# 03_-_CPU_-_DDR3_DDR3_MEM.net
KiCad netlist of a schematic drawn in Altium Designer
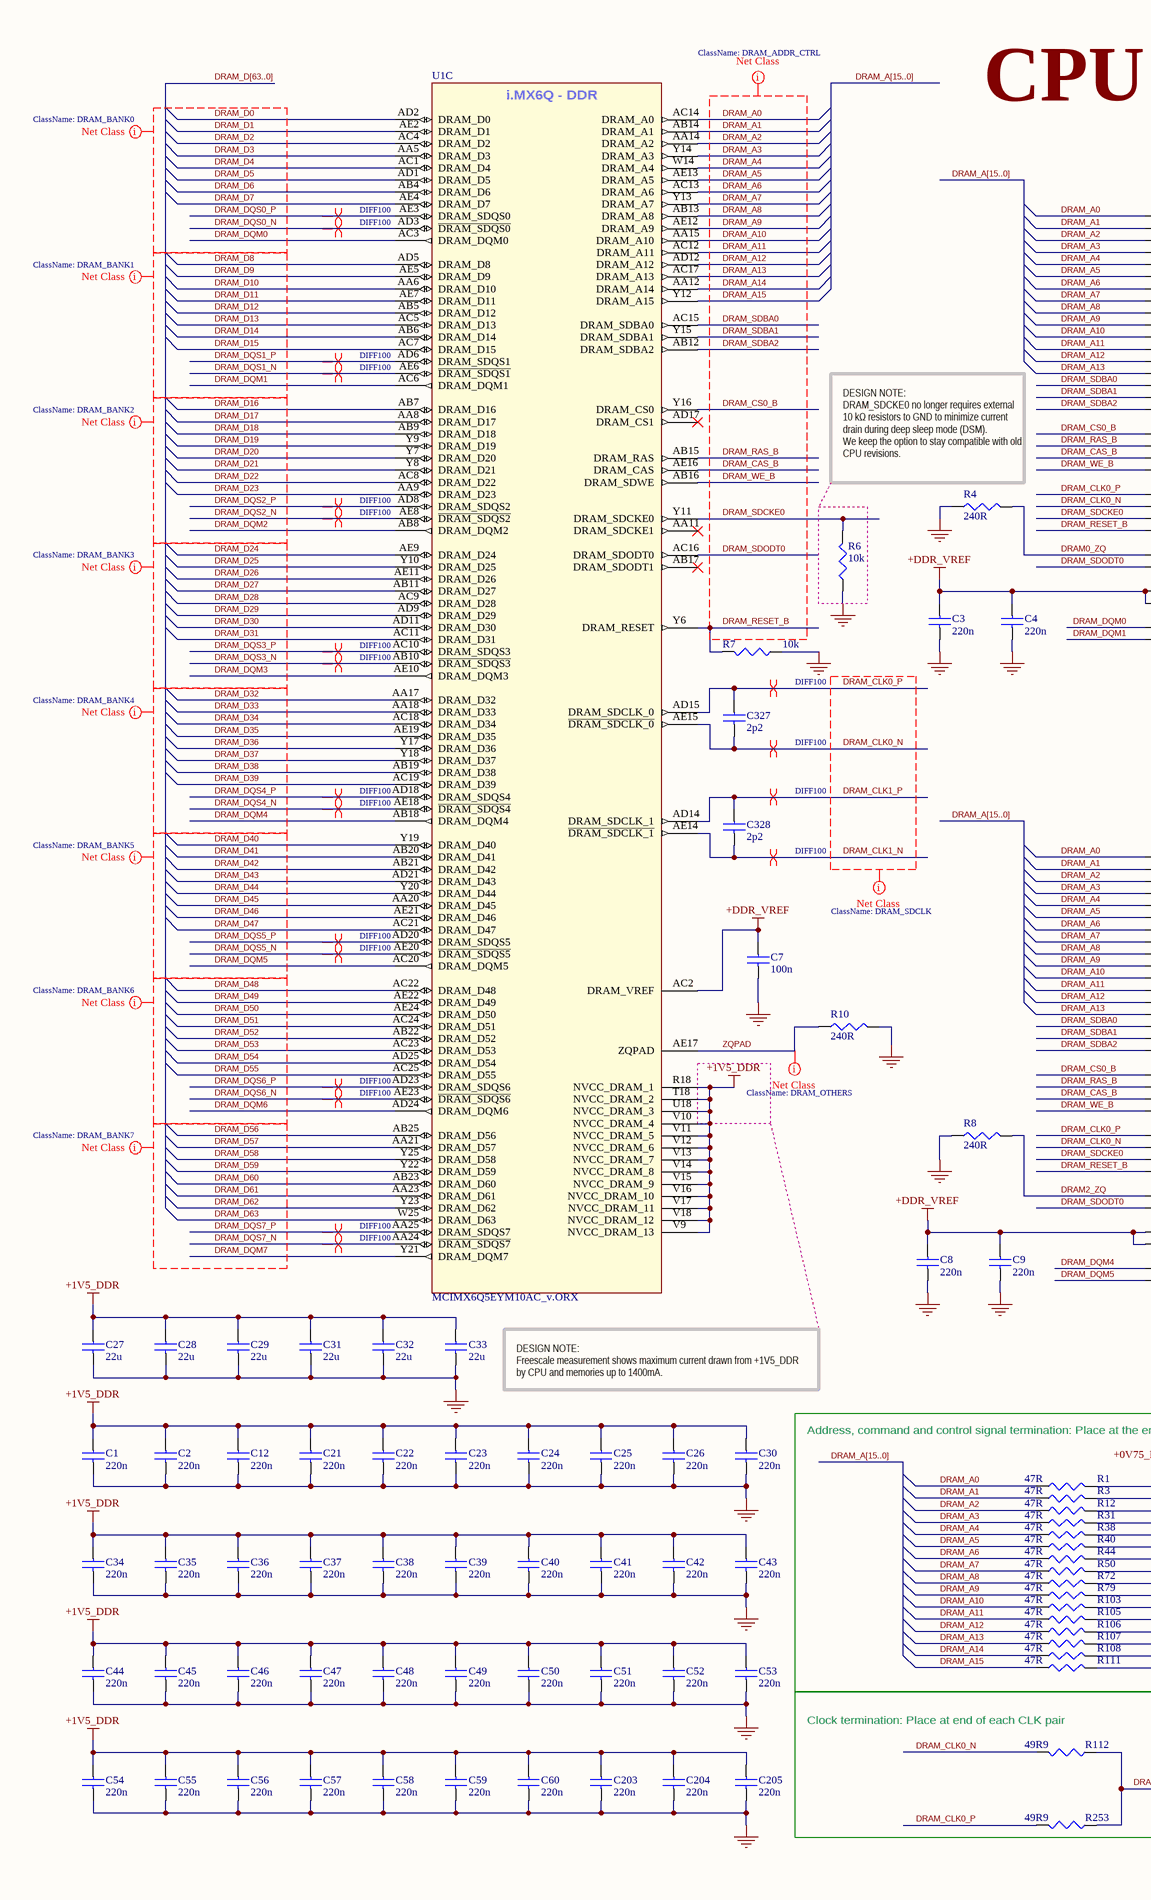
[diagram p0: [03] - CPU - DDR3, DDR3 MEM.SchDoc, left]
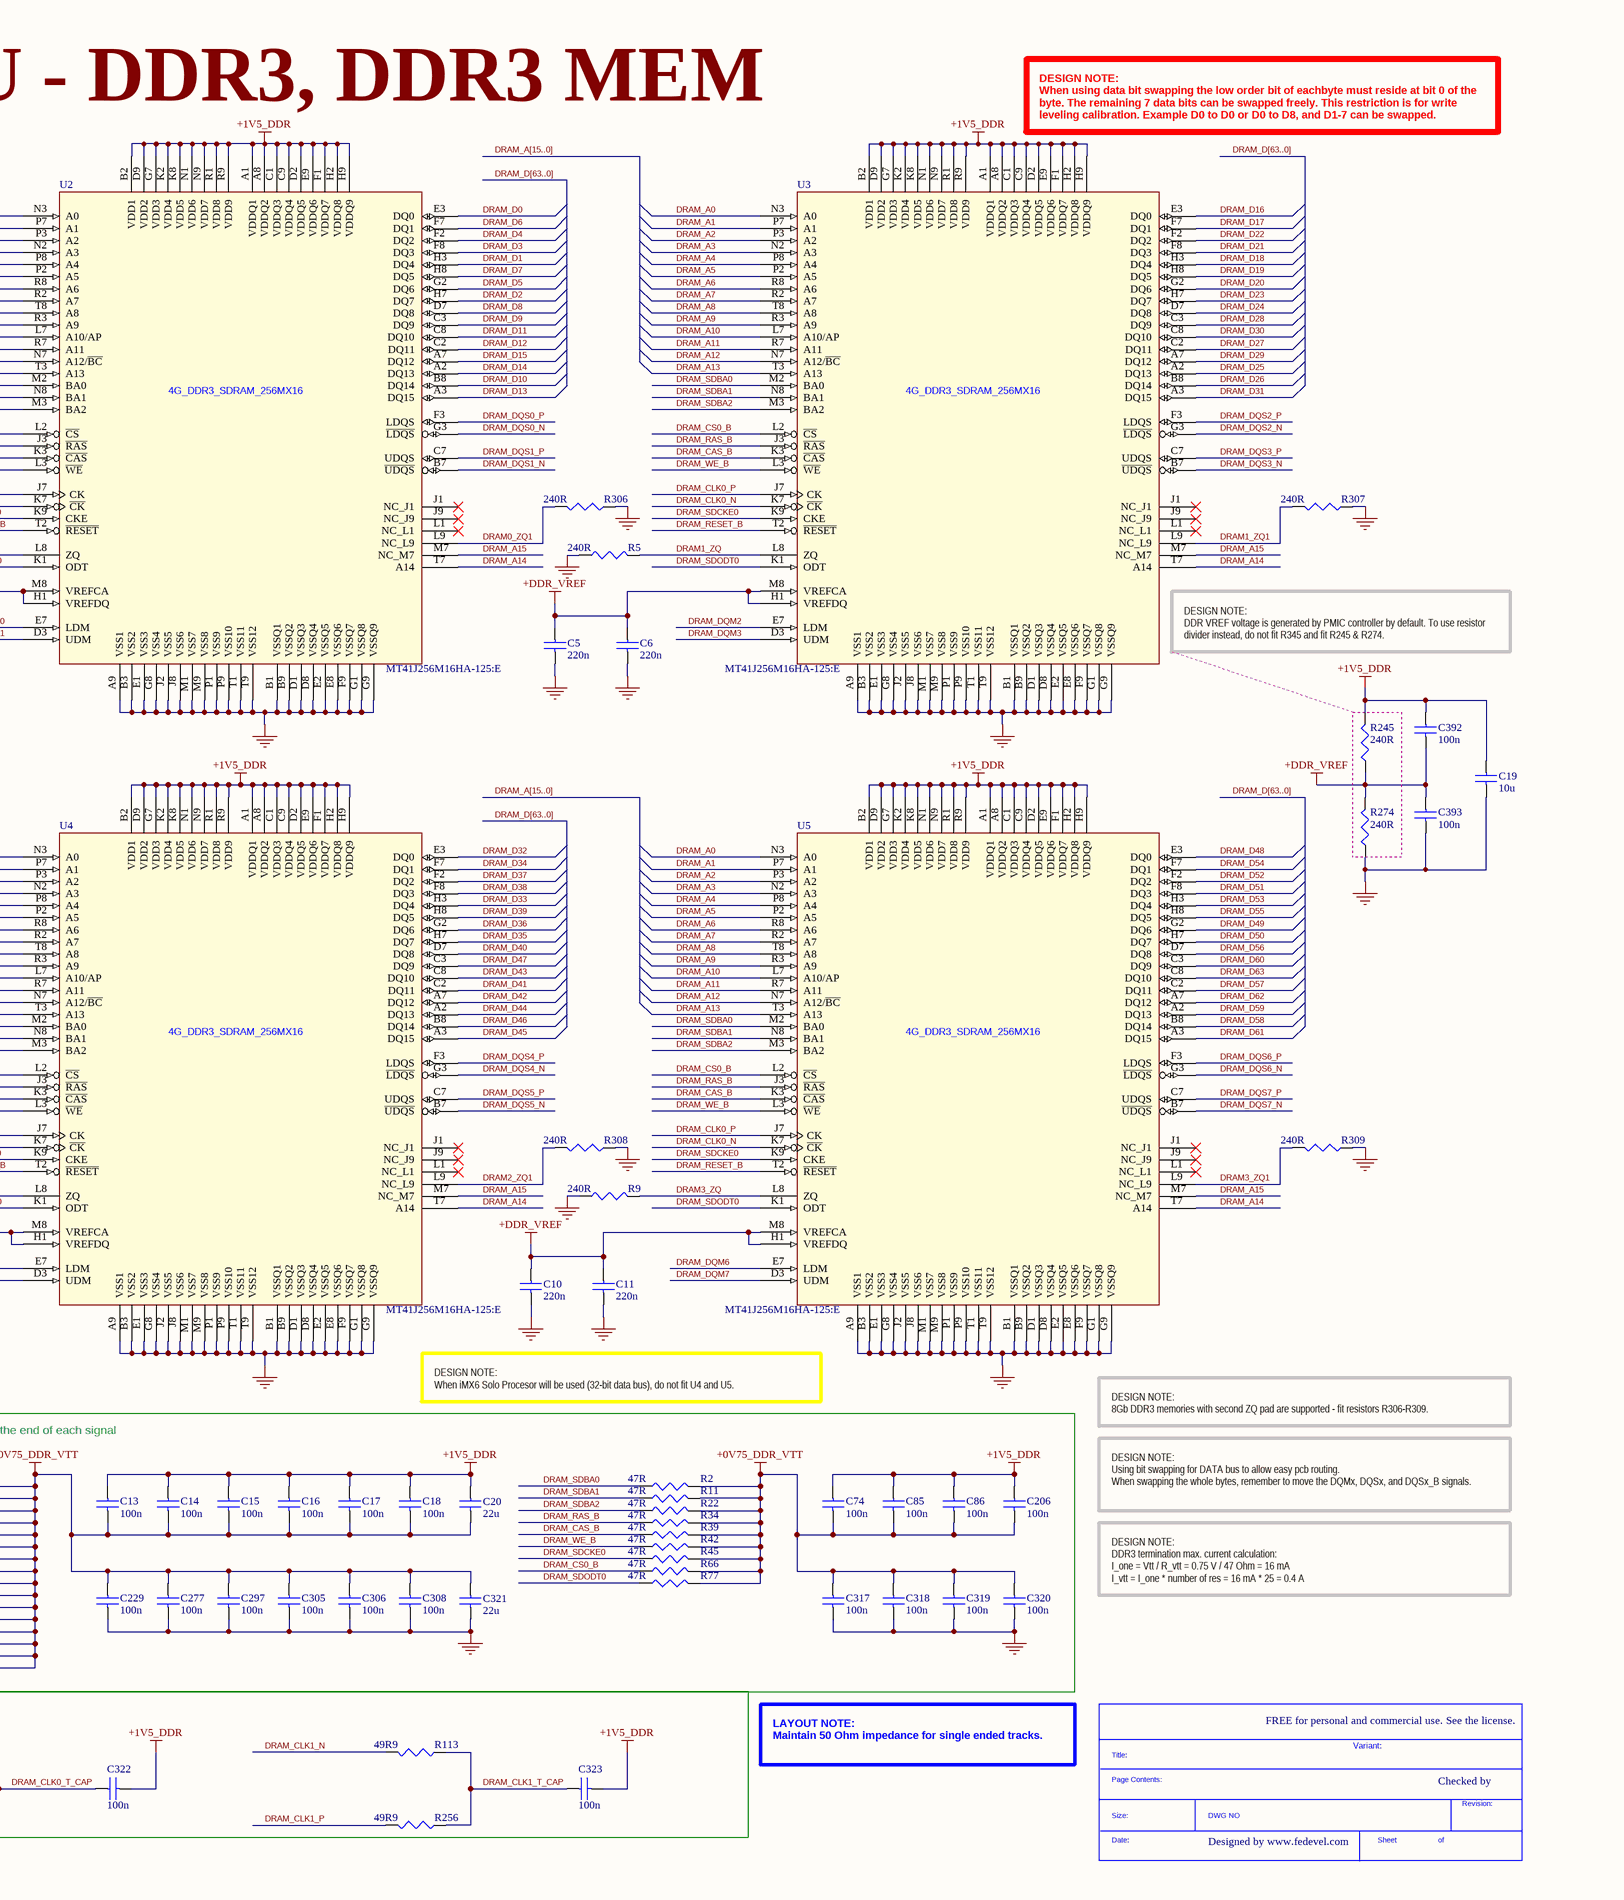
[diagram p1: [03] - CPU - DDR3, DDR3 MEM.SchDoc, right]

(export (version "E")
  (design (tool "Eeschema 10.0.6"))
  (components
    (comp (ref "C1")
      (value "220n")
      (footprint "C0201")
      (description "CAP CER 0.22UF 6.3V 20% X5R 0201")
      (fields
        (field (name "MANUFACTURER") "TDK Corporation")
        (field (name "MANUFACTURER PART NUMBER") "C0603X5R0J224M030BB")
        (field (name ".CHECKED PCB") "MM")
        (field (name ".CHECKED SCH") "MM")
        (field (name ".CREATOR") "MM")
      )
      (libsource (lib "Integrated_Library_FEDEVEL_0201") (part "C0603X5R0J224M030BB"))
    )
    (comp (ref "C2")
      (value "220n")
      (footprint "C0201")
      (description "CAP CER 0.22UF 6.3V 20% X5R 0201")
      (fields
        (field (name "MANUFACTURER") "TDK Corporation")
        (field (name "MANUFACTURER PART NUMBER") "C0603X5R0J224M030BB")
        (field (name ".CHECKED PCB") "MM")
        (field (name ".CHECKED SCH") "MM")
        (field (name ".CREATOR") "MM")
      )
      (libsource (lib "Integrated_Library_FEDEVEL_0201") (part "C0603X5R0J224M030BB"))
    )
    (comp (ref "C3")
      (value "220n")
      (footprint "C0201")
      (description "CAP CER 0.22UF 6.3V 20% X5R 0201")
      (fields
        (field (name "MANUFACTURER") "TDK Corporation")
        (field (name "MANUFACTURER PART NUMBER") "C0603X5R0J224M030BB")
        (field (name ".CHECKED PCB") "MM")
        (field (name ".CHECKED SCH") "MM")
        (field (name ".CREATOR") "MM")
      )
      (libsource (lib "Integrated_Library_FEDEVEL_0201") (part "C0603X5R0J224M030BB"))
    )
    (comp (ref "C4")
      (value "220n")
      (footprint "C0201")
      (description "CAP CER 0.22UF 6.3V 20% X5R 0201")
      (fields
        (field (name "MANUFACTURER") "TDK Corporation")
        (field (name "MANUFACTURER PART NUMBER") "C0603X5R0J224M030BB")
        (field (name ".CHECKED PCB") "MM")
        (field (name ".CHECKED SCH") "MM")
        (field (name ".CREATOR") "MM")
      )
      (libsource (lib "Integrated_Library_FEDEVEL_0201") (part "C0603X5R0J224M030BB"))
    )
    (comp (ref "C5")
      (value "220n")
      (footprint "C0201")
      (description "CAP CER 0.22UF 6.3V 20% X5R 0201")
      (fields
        (field (name "MANUFACTURER") "TDK Corporation")
        (field (name "MANUFACTURER PART NUMBER") "C0603X5R0J224M030BB")
        (field (name ".CHECKED PCB") "MM")
        (field (name ".CHECKED SCH") "MM")
        (field (name ".CREATOR") "MM")
      )
      (libsource (lib "Integrated_Library_FEDEVEL_0201") (part "C0603X5R0J224M030BB"))
    )
    (comp (ref "C6")
      (value "220n")
      (footprint "C0201")
      (description "CAP CER 0.22UF 6.3V 20% X5R 0201")
      (fields
        (field (name "MANUFACTURER") "TDK Corporation")
        (field (name "MANUFACTURER PART NUMBER") "C0603X5R0J224M030BB")
        (field (name ".CHECKED PCB") "MM")
        (field (name ".CHECKED SCH") "MM")
        (field (name ".CREATOR") "MM")
      )
      (libsource (lib "Integrated_Library_FEDEVEL_0201") (part "C0603X5R0J224M030BB"))
    )
    (comp (ref "C7")
      (value "100n")
      (footprint "C0201")
      (description "CAP CER 0.1UF 16V 10% X5R 0201")
      (fields
        (field (name "MANUFACTURER") "TDK Corporation")
        (field (name "MANUFACTURER PART NUMBER") "C0603X5R1C104K030BC")
        (field (name ".CREATOR") "MM")
        (field (name ".CHECKED PCB") "MM")
        (field (name ".CHECKED SCH") "MM")
      )
      (libsource (lib "Integrated_Library_FEDEVEL_0201") (part "C0603X5R1C104K030BC"))
    )
    (comp (ref "C8")
      (value "220n")
      (footprint "C0201")
      (description "CAP CER 0.22UF 6.3V 20% X5R 0201")
      (fields
        (field (name "MANUFACTURER") "TDK Corporation")
        (field (name "MANUFACTURER PART NUMBER") "C0603X5R0J224M030BB")
        (field (name ".CHECKED PCB") "MM")
        (field (name ".CHECKED SCH") "MM")
        (field (name ".CREATOR") "MM")
      )
      (libsource (lib "Integrated_Library_FEDEVEL_0201") (part "C0603X5R0J224M030BB"))
    )
    (comp (ref "C9")
      (value "220n")
      (footprint "C0201")
      (description "CAP CER 0.22UF 6.3V 20% X5R 0201")
      (fields
        (field (name "MANUFACTURER") "TDK Corporation")
        (field (name "MANUFACTURER PART NUMBER") "C0603X5R0J224M030BB")
        (field (name ".CHECKED PCB") "MM")
        (field (name ".CHECKED SCH") "MM")
        (field (name ".CREATOR") "MM")
      )
      (libsource (lib "Integrated_Library_FEDEVEL_0201") (part "C0603X5R0J224M030BB"))
    )
    (comp (ref "C10")
      (value "220n")
      (footprint "C0201")
      (description "CAP CER 0.22UF 6.3V 20% X5R 0201")
      (fields
        (field (name "MANUFACTURER") "TDK Corporation")
        (field (name "MANUFACTURER PART NUMBER") "C0603X5R0J224M030BB")
        (field (name ".CHECKED PCB") "MM")
        (field (name ".CHECKED SCH") "MM")
        (field (name ".CREATOR") "MM")
      )
      (libsource (lib "Integrated_Library_FEDEVEL_0201") (part "C0603X5R0J224M030BB"))
    )
    (comp (ref "C11")
      (value "220n")
      (footprint "C0201")
      (description "CAP CER 0.22UF 6.3V 20% X5R 0201")
      (fields
        (field (name "MANUFACTURER") "TDK Corporation")
        (field (name "MANUFACTURER PART NUMBER") "C0603X5R0J224M030BB")
        (field (name ".CHECKED PCB") "MM")
        (field (name ".CHECKED SCH") "MM")
        (field (name ".CREATOR") "MM")
      )
      (libsource (lib "Integrated_Library_FEDEVEL_0201") (part "C0603X5R0J224M030BB"))
    )
    (comp (ref "C12")
      (value "220n")
      (footprint "C0201")
      (description "CAP CER 0.22UF 6.3V 20% X5R 0201")
      (fields
        (field (name "MANUFACTURER") "TDK Corporation")
        (field (name "MANUFACTURER PART NUMBER") "C0603X5R0J224M030BB")
        (field (name ".CHECKED PCB") "MM")
        (field (name ".CHECKED SCH") "MM")
        (field (name ".CREATOR") "MM")
      )
      (libsource (lib "Integrated_Library_FEDEVEL_0201") (part "C0603X5R0J224M030BB"))
    )
    (comp (ref "C13")
      (value "100n")
      (footprint "C0201")
      (description "CAP CER 0.1UF 16V 10% X5R 0201")
      (fields
        (field (name "MANUFACTURER") "TDK Corporation")
        (field (name "MANUFACTURER PART NUMBER") "C0603X5R1C104K030BC")
        (field (name ".CREATOR") "MM")
        (field (name ".CHECKED PCB") "MM")
        (field (name ".CHECKED SCH") "MM")
      )
      (libsource (lib "Integrated_Library_FEDEVEL_0201") (part "C0603X5R1C104K030BC"))
    )
    (comp (ref "C14")
      (value "100n")
      (footprint "C0201")
      (description "CAP CER 0.1UF 16V 10% X5R 0201")
      (fields
        (field (name "MANUFACTURER") "TDK Corporation")
        (field (name "MANUFACTURER PART NUMBER") "C0603X5R1C104K030BC")
        (field (name ".CREATOR") "MM")
        (field (name ".CHECKED PCB") "MM")
        (field (name ".CHECKED SCH") "MM")
      )
      (libsource (lib "Integrated_Library_FEDEVEL_0201") (part "C0603X5R1C104K030BC"))
    )
    (comp (ref "C15")
      (value "100n")
      (footprint "C0201")
      (description "CAP CER 0.1UF 16V 10% X5R 0201")
      (fields
        (field (name "MANUFACTURER") "TDK Corporation")
        (field (name "MANUFACTURER PART NUMBER") "C0603X5R1C104K030BC")
        (field (name ".CREATOR") "MM")
        (field (name ".CHECKED PCB") "MM")
        (field (name ".CHECKED SCH") "MM")
      )
      (libsource (lib "Integrated_Library_FEDEVEL_0201") (part "C0603X5R1C104K030BC"))
    )
    (comp (ref "C16")
      (value "100n")
      (footprint "C0201")
      (description "CAP CER 0.1UF 16V 10% X5R 0201")
      (fields
        (field (name "MANUFACTURER") "TDK Corporation")
        (field (name "MANUFACTURER PART NUMBER") "C0603X5R1C104K030BC")
        (field (name ".CREATOR") "MM")
        (field (name ".CHECKED PCB") "MM")
        (field (name ".CHECKED SCH") "MM")
      )
      (libsource (lib "Integrated_Library_FEDEVEL_0201") (part "C0603X5R1C104K030BC"))
    )
    (comp (ref "C17")
      (value "100n")
      (footprint "C0201")
      (description "CAP CER 0.1UF 16V 10% X5R 0201")
      (fields
        (field (name "MANUFACTURER") "TDK Corporation")
        (field (name "MANUFACTURER PART NUMBER") "C0603X5R1C104K030BC")
        (field (name ".CREATOR") "MM")
        (field (name ".CHECKED PCB") "MM")
        (field (name ".CHECKED SCH") "MM")
      )
      (libsource (lib "Integrated_Library_FEDEVEL_0201") (part "C0603X5R1C104K030BC"))
    )
    (comp (ref "C18")
      (value "100n")
      (footprint "C0201")
      (description "CAP CER 0.1UF 16V 10% X5R 0201")
      (fields
        (field (name "MANUFACTURER") "TDK Corporation")
        (field (name "MANUFACTURER PART NUMBER") "C0603X5R1C104K030BC")
        (field (name ".CREATOR") "MM")
        (field (name ".CHECKED PCB") "MM")
        (field (name ".CHECKED SCH") "MM")
      )
      (libsource (lib "Integrated_Library_FEDEVEL_0201") (part "C0603X5R1C104K030BC"))
    )
    (comp (ref "C19")
      (value "10u")
      (footprint "C0603")
      (description "CAP CER 10UF 6.3V X5R 20% 0603")
      (fields
        (field (name "MANUFACTURER") "TDK Corporation")
        (field (name "MANUFACTURER PART NUMBER") "C1608X5R0J106M")
      )
      (libsource (lib "Integrated_Library_FEDEVEL_APR_2015") (part "C1608X5R0J106M"))
    )
    (comp (ref "C20")
      (value "22u")
      (footprint "C0603")
      (description "CAP CER 22UF 4V 20% X5R 0603")
      (fields
        (field (name "MANUFACTURER") "Murata Electronics North America")
        (field (name "MANUFACTURER PART NUMBER") "GRM188R60G226MEA0L")
        (field (name ".CREATOR") "MM")
      )
      (libsource (lib "Integrated_Library_FEDEVEL_APR_2015") (part "GRM188R60G226MEA0L"))
    )
    (comp (ref "C21")
      (value "220n")
      (footprint "C0201")
      (description "CAP CER 0.22UF 6.3V 20% X5R 0201")
      (fields
        (field (name "MANUFACTURER") "TDK Corporation")
        (field (name "MANUFACTURER PART NUMBER") "C0603X5R0J224M030BB")
        (field (name ".CHECKED PCB") "MM")
        (field (name ".CHECKED SCH") "MM")
        (field (name ".CREATOR") "MM")
      )
      (libsource (lib "Integrated_Library_FEDEVEL_0201") (part "C0603X5R0J224M030BB"))
    )
    (comp (ref "C22")
      (value "220n")
      (footprint "C0201")
      (description "CAP CER 0.22UF 6.3V 20% X5R 0201")
      (fields
        (field (name "MANUFACTURER") "TDK Corporation")
        (field (name "MANUFACTURER PART NUMBER") "C0603X5R0J224M030BB")
        (field (name ".CHECKED PCB") "MM")
        (field (name ".CHECKED SCH") "MM")
        (field (name ".CREATOR") "MM")
      )
      (libsource (lib "Integrated_Library_FEDEVEL_0201") (part "C0603X5R0J224M030BB"))
    )
    (comp (ref "C23")
      (value "220n")
      (footprint "C0201")
      (description "CAP CER 0.22UF 6.3V 20% X5R 0201")
      (fields
        (field (name "MANUFACTURER") "TDK Corporation")
        (field (name "MANUFACTURER PART NUMBER") "C0603X5R0J224M030BB")
        (field (name ".CHECKED PCB") "MM")
        (field (name ".CHECKED SCH") "MM")
        (field (name ".CREATOR") "MM")
      )
      (libsource (lib "Integrated_Library_FEDEVEL_0201") (part "C0603X5R0J224M030BB"))
    )
    (comp (ref "C24")
      (value "220n")
      (footprint "C0201")
      (description "CAP CER 0.22UF 6.3V 20% X5R 0201")
      (fields
        (field (name "MANUFACTURER") "TDK Corporation")
        (field (name "MANUFACTURER PART NUMBER") "C0603X5R0J224M030BB")
        (field (name ".CHECKED PCB") "MM")
        (field (name ".CHECKED SCH") "MM")
        (field (name ".CREATOR") "MM")
      )
      (libsource (lib "Integrated_Library_FEDEVEL_0201") (part "C0603X5R0J224M030BB"))
    )
    (comp (ref "C25")
      (value "220n")
      (footprint "C0201")
      (description "CAP CER 0.22UF 6.3V 20% X5R 0201")
      (fields
        (field (name "MANUFACTURER") "TDK Corporation")
        (field (name "MANUFACTURER PART NUMBER") "C0603X5R0J224M030BB")
        (field (name ".CHECKED PCB") "MM")
        (field (name ".CHECKED SCH") "MM")
        (field (name ".CREATOR") "MM")
      )
      (libsource (lib "Integrated_Library_FEDEVEL_0201") (part "C0603X5R0J224M030BB"))
    )
    (comp (ref "C26")
      (value "220n")
      (footprint "C0201")
      (description "CAP CER 0.22UF 6.3V 20% X5R 0201")
      (fields
        (field (name "MANUFACTURER") "TDK Corporation")
        (field (name "MANUFACTURER PART NUMBER") "C0603X5R0J224M030BB")
        (field (name ".CHECKED PCB") "MM")
        (field (name ".CHECKED SCH") "MM")
        (field (name ".CREATOR") "MM")
      )
      (libsource (lib "Integrated_Library_FEDEVEL_0201") (part "C0603X5R0J224M030BB"))
    )
    (comp (ref "C27")
      (value "22u")
      (footprint "C0603")
      (description "CAP CER 22UF 4V 20% X5R 0603")
      (fields
        (field (name "MANUFACTURER") "Murata Electronics North America")
        (field (name "MANUFACTURER PART NUMBER") "GRM188R60G226MEA0L")
        (field (name ".CREATOR") "MM")
      )
      (libsource (lib "Integrated_Library_FEDEVEL_APR_2015") (part "GRM188R60G226MEA0L"))
    )
    (comp (ref "C28")
      (value "22u")
      (footprint "C0603")
      (description "CAP CER 22UF 4V 20% X5R 0603")
      (fields
        (field (name "MANUFACTURER") "Murata Electronics North America")
        (field (name "MANUFACTURER PART NUMBER") "GRM188R60G226MEA0L")
        (field (name ".CREATOR") "MM")
      )
      (libsource (lib "Integrated_Library_FEDEVEL_APR_2015") (part "GRM188R60G226MEA0L"))
    )
    (comp (ref "C29")
      (value "22u")
      (footprint "C0603")
      (description "CAP CER 22UF 4V 20% X5R 0603")
      (fields
        (field (name "MANUFACTURER") "Murata Electronics North America")
        (field (name "MANUFACTURER PART NUMBER") "GRM188R60G226MEA0L")
        (field (name ".CREATOR") "MM")
      )
      (libsource (lib "Integrated_Library_FEDEVEL_APR_2015") (part "GRM188R60G226MEA0L"))
    )
    (comp (ref "C30")
      (value "220n")
      (footprint "C0201")
      (description "CAP CER 0.22UF 6.3V 20% X5R 0201")
      (fields
        (field (name "MANUFACTURER") "TDK Corporation")
        (field (name "MANUFACTURER PART NUMBER") "C0603X5R0J224M030BB")
        (field (name ".CHECKED PCB") "MM")
        (field (name ".CHECKED SCH") "MM")
        (field (name ".CREATOR") "MM")
      )
      (libsource (lib "Integrated_Library_FEDEVEL_0201") (part "C0603X5R0J224M030BB"))
    )
    (comp (ref "C31")
      (value "22u")
      (footprint "C0603")
      (description "CAP CER 22UF 4V 20% X5R 0603")
      (fields
        (field (name "MANUFACTURER") "Murata Electronics North America")
        (field (name "MANUFACTURER PART NUMBER") "GRM188R60G226MEA0L")
        (field (name ".CREATOR") "MM")
      )
      (libsource (lib "Integrated_Library_FEDEVEL_APR_2015") (part "GRM188R60G226MEA0L"))
    )
    (comp (ref "C32")
      (value "22u")
      (footprint "C0603")
      (description "CAP CER 22UF 4V 20% X5R 0603")
      (fields
        (field (name "MANUFACTURER") "Murata Electronics North America")
        (field (name "MANUFACTURER PART NUMBER") "GRM188R60G226MEA0L")
        (field (name ".CREATOR") "MM")
      )
      (libsource (lib "Integrated_Library_FEDEVEL_APR_2015") (part "GRM188R60G226MEA0L"))
    )
    (comp (ref "C33")
      (value "22u")
      (footprint "C0603")
      (description "CAP CER 22UF 4V 20% X5R 0603")
      (fields
        (field (name "MANUFACTURER") "Murata Electronics North America")
        (field (name "MANUFACTURER PART NUMBER") "GRM188R60G226MEA0L")
        (field (name ".CREATOR") "MM")
      )
      (libsource (lib "Integrated_Library_FEDEVEL_APR_2015") (part "GRM188R60G226MEA0L"))
    )
    (comp (ref "C34")
      (value "220n")
      (footprint "C0201")
      (description "CAP CER 0.22UF 6.3V 20% X5R 0201")
      (fields
        (field (name "MANUFACTURER") "TDK Corporation")
        (field (name "MANUFACTURER PART NUMBER") "C0603X5R0J224M030BB")
        (field (name ".CHECKED PCB") "MM")
        (field (name ".CHECKED SCH") "MM")
        (field (name ".CREATOR") "MM")
      )
      (libsource (lib "Integrated_Library_FEDEVEL_0201") (part "C0603X5R0J224M030BB"))
    )
    (comp (ref "C35")
      (value "220n")
      (footprint "C0201")
      (description "CAP CER 0.22UF 6.3V 20% X5R 0201")
      (fields
        (field (name "MANUFACTURER") "TDK Corporation")
        (field (name "MANUFACTURER PART NUMBER") "C0603X5R0J224M030BB")
        (field (name ".CHECKED PCB") "MM")
        (field (name ".CHECKED SCH") "MM")
        (field (name ".CREATOR") "MM")
      )
      (libsource (lib "Integrated_Library_FEDEVEL_0201") (part "C0603X5R0J224M030BB"))
    )
    (comp (ref "C36")
      (value "220n")
      (footprint "C0201")
      (description "CAP CER 0.22UF 6.3V 20% X5R 0201")
      (fields
        (field (name "MANUFACTURER") "TDK Corporation")
        (field (name "MANUFACTURER PART NUMBER") "C0603X5R0J224M030BB")
        (field (name ".CHECKED PCB") "MM")
        (field (name ".CHECKED SCH") "MM")
        (field (name ".CREATOR") "MM")
      )
      (libsource (lib "Integrated_Library_FEDEVEL_0201") (part "C0603X5R0J224M030BB"))
    )
    (comp (ref "C37")
      (value "220n")
      (footprint "C0201")
      (description "CAP CER 0.22UF 6.3V 20% X5R 0201")
      (fields
        (field (name "MANUFACTURER") "TDK Corporation")
        (field (name "MANUFACTURER PART NUMBER") "C0603X5R0J224M030BB")
        (field (name ".CHECKED PCB") "MM")
        (field (name ".CHECKED SCH") "MM")
        (field (name ".CREATOR") "MM")
      )
      (libsource (lib "Integrated_Library_FEDEVEL_0201") (part "C0603X5R0J224M030BB"))
    )
    (comp (ref "C38")
      (value "220n")
      (footprint "C0201")
      (description "CAP CER 0.22UF 6.3V 20% X5R 0201")
      (fields
        (field (name "MANUFACTURER") "TDK Corporation")
        (field (name "MANUFACTURER PART NUMBER") "C0603X5R0J224M030BB")
        (field (name ".CHECKED PCB") "MM")
        (field (name ".CHECKED SCH") "MM")
        (field (name ".CREATOR") "MM")
      )
      (libsource (lib "Integrated_Library_FEDEVEL_0201") (part "C0603X5R0J224M030BB"))
    )
    (comp (ref "C39")
      (value "220n")
      (footprint "C0201")
      (description "CAP CER 0.22UF 6.3V 20% X5R 0201")
      (fields
        (field (name "MANUFACTURER") "TDK Corporation")
        (field (name "MANUFACTURER PART NUMBER") "C0603X5R0J224M030BB")
        (field (name ".CHECKED PCB") "MM")
        (field (name ".CHECKED SCH") "MM")
        (field (name ".CREATOR") "MM")
      )
      (libsource (lib "Integrated_Library_FEDEVEL_0201") (part "C0603X5R0J224M030BB"))
    )
    (comp (ref "C40")
      (value "220n")
      (footprint "C0201")
      (description "CAP CER 0.22UF 6.3V 20% X5R 0201")
      (fields
        (field (name "MANUFACTURER") "TDK Corporation")
        (field (name "MANUFACTURER PART NUMBER") "C0603X5R0J224M030BB")
        (field (name ".CHECKED PCB") "MM")
        (field (name ".CHECKED SCH") "MM")
        (field (name ".CREATOR") "MM")
      )
      (libsource (lib "Integrated_Library_FEDEVEL_0201") (part "C0603X5R0J224M030BB"))
    )
    (comp (ref "C41")
      (value "220n")
      (footprint "C0201")
      (description "CAP CER 0.22UF 6.3V 20% X5R 0201")
      (fields
        (field (name "MANUFACTURER") "TDK Corporation")
        (field (name "MANUFACTURER PART NUMBER") "C0603X5R0J224M030BB")
        (field (name ".CHECKED PCB") "MM")
        (field (name ".CHECKED SCH") "MM")
        (field (name ".CREATOR") "MM")
      )
      (libsource (lib "Integrated_Library_FEDEVEL_0201") (part "C0603X5R0J224M030BB"))
    )
    (comp (ref "C42")
      (value "220n")
      (footprint "C0201")
      (description "CAP CER 0.22UF 6.3V 20% X5R 0201")
      (fields
        (field (name "MANUFACTURER") "TDK Corporation")
        (field (name "MANUFACTURER PART NUMBER") "C0603X5R0J224M030BB")
        (field (name ".CHECKED PCB") "MM")
        (field (name ".CHECKED SCH") "MM")
        (field (name ".CREATOR") "MM")
      )
      (libsource (lib "Integrated_Library_FEDEVEL_0201") (part "C0603X5R0J224M030BB"))
    )
    (comp (ref "C43")
      (value "220n")
      (footprint "C0201")
      (description "CAP CER 0.22UF 6.3V 20% X5R 0201")
      (fields
        (field (name "MANUFACTURER") "TDK Corporation")
        (field (name "MANUFACTURER PART NUMBER") "C0603X5R0J224M030BB")
        (field (name ".CHECKED PCB") "MM")
        (field (name ".CHECKED SCH") "MM")
        (field (name ".CREATOR") "MM")
      )
      (libsource (lib "Integrated_Library_FEDEVEL_0201") (part "C0603X5R0J224M030BB"))
    )
    (comp (ref "C44")
      (value "220n")
      (footprint "C0201")
      (description "CAP CER 0.22UF 6.3V 20% X5R 0201")
      (fields
        (field (name "MANUFACTURER") "TDK Corporation")
        (field (name "MANUFACTURER PART NUMBER") "C0603X5R0J224M030BB")
        (field (name ".CHECKED PCB") "MM")
        (field (name ".CHECKED SCH") "MM")
        (field (name ".CREATOR") "MM")
      )
      (libsource (lib "Integrated_Library_FEDEVEL_0201") (part "C0603X5R0J224M030BB"))
    )
    (comp (ref "C45")
      (value "220n")
      (footprint "C0201")
      (description "CAP CER 0.22UF 6.3V 20% X5R 0201")
      (fields
        (field (name "MANUFACTURER") "TDK Corporation")
        (field (name "MANUFACTURER PART NUMBER") "C0603X5R0J224M030BB")
        (field (name ".CHECKED PCB") "MM")
        (field (name ".CHECKED SCH") "MM")
        (field (name ".CREATOR") "MM")
      )
      (libsource (lib "Integrated_Library_FEDEVEL_0201") (part "C0603X5R0J224M030BB"))
    )
    (comp (ref "C46")
      (value "220n")
      (footprint "C0201")
      (description "CAP CER 0.22UF 6.3V 20% X5R 0201")
      (fields
        (field (name "MANUFACTURER") "TDK Corporation")
        (field (name "MANUFACTURER PART NUMBER") "C0603X5R0J224M030BB")
        (field (name ".CHECKED PCB") "MM")
        (field (name ".CHECKED SCH") "MM")
        (field (name ".CREATOR") "MM")
      )
      (libsource (lib "Integrated_Library_FEDEVEL_0201") (part "C0603X5R0J224M030BB"))
    )
    (comp (ref "C47")
      (value "220n")
      (footprint "C0201")
      (description "CAP CER 0.22UF 6.3V 20% X5R 0201")
      (fields
        (field (name "MANUFACTURER") "TDK Corporation")
        (field (name "MANUFACTURER PART NUMBER") "C0603X5R0J224M030BB")
        (field (name ".CHECKED PCB") "MM")
        (field (name ".CHECKED SCH") "MM")
        (field (name ".CREATOR") "MM")
      )
      (libsource (lib "Integrated_Library_FEDEVEL_0201") (part "C0603X5R0J224M030BB"))
    )
    (comp (ref "C48")
      (value "220n")
      (footprint "C0201")
      (description "CAP CER 0.22UF 6.3V 20% X5R 0201")
      (fields
        (field (name "MANUFACTURER") "TDK Corporation")
        (field (name "MANUFACTURER PART NUMBER") "C0603X5R0J224M030BB")
        (field (name ".CHECKED PCB") "MM")
        (field (name ".CHECKED SCH") "MM")
        (field (name ".CREATOR") "MM")
      )
      (libsource (lib "Integrated_Library_FEDEVEL_0201") (part "C0603X5R0J224M030BB"))
    )
    (comp (ref "C49")
      (value "220n")
      (footprint "C0201")
      (description "CAP CER 0.22UF 6.3V 20% X5R 0201")
      (fields
        (field (name "MANUFACTURER") "TDK Corporation")
        (field (name "MANUFACTURER PART NUMBER") "C0603X5R0J224M030BB")
        (field (name ".CHECKED PCB") "MM")
        (field (name ".CHECKED SCH") "MM")
        (field (name ".CREATOR") "MM")
      )
      (libsource (lib "Integrated_Library_FEDEVEL_0201") (part "C0603X5R0J224M030BB"))
    )
    (comp (ref "C50")
      (value "220n")
      (footprint "C0201")
      (description "CAP CER 0.22UF 6.3V 20% X5R 0201")
      (fields
        (field (name "MANUFACTURER") "TDK Corporation")
        (field (name "MANUFACTURER PART NUMBER") "C0603X5R0J224M030BB")
        (field (name ".CHECKED PCB") "MM")
        (field (name ".CHECKED SCH") "MM")
        (field (name ".CREATOR") "MM")
      )
      (libsource (lib "Integrated_Library_FEDEVEL_0201") (part "C0603X5R0J224M030BB"))
    )
    (comp (ref "C51")
      (value "220n")
      (footprint "C0201")
      (description "CAP CER 0.22UF 6.3V 20% X5R 0201")
      (fields
        (field (name "MANUFACTURER") "TDK Corporation")
        (field (name "MANUFACTURER PART NUMBER") "C0603X5R0J224M030BB")
        (field (name ".CHECKED PCB") "MM")
        (field (name ".CHECKED SCH") "MM")
        (field (name ".CREATOR") "MM")
      )
      (libsource (lib "Integrated_Library_FEDEVEL_0201") (part "C0603X5R0J224M030BB"))
    )
    (comp (ref "C52")
      (value "220n")
      (footprint "C0201")
      (description "CAP CER 0.22UF 6.3V 20% X5R 0201")
      (fields
        (field (name "MANUFACTURER") "TDK Corporation")
        (field (name "MANUFACTURER PART NUMBER") "C0603X5R0J224M030BB")
        (field (name ".CHECKED PCB") "MM")
        (field (name ".CHECKED SCH") "MM")
        (field (name ".CREATOR") "MM")
      )
      (libsource (lib "Integrated_Library_FEDEVEL_0201") (part "C0603X5R0J224M030BB"))
    )
    (comp (ref "C53")
      (value "220n")
      (footprint "C0201")
      (description "CAP CER 0.22UF 6.3V 20% X5R 0201")
      (fields
        (field (name "MANUFACTURER") "TDK Corporation")
        (field (name "MANUFACTURER PART NUMBER") "C0603X5R0J224M030BB")
        (field (name ".CHECKED PCB") "MM")
        (field (name ".CHECKED SCH") "MM")
        (field (name ".CREATOR") "MM")
      )
      (libsource (lib "Integrated_Library_FEDEVEL_0201") (part "C0603X5R0J224M030BB"))
    )
    (comp (ref "C54")
      (value "220n")
      (footprint "C0201")
      (description "CAP CER 0.22UF 6.3V 20% X5R 0201")
      (fields
        (field (name "MANUFACTURER") "TDK Corporation")
        (field (name "MANUFACTURER PART NUMBER") "C0603X5R0J224M030BB")
        (field (name ".CHECKED PCB") "MM")
        (field (name ".CHECKED SCH") "MM")
        (field (name ".CREATOR") "MM")
      )
      (libsource (lib "Integrated_Library_FEDEVEL_0201") (part "C0603X5R0J224M030BB"))
    )
    (comp (ref "C55")
      (value "220n")
      (footprint "C0201")
      (description "CAP CER 0.22UF 6.3V 20% X5R 0201")
      (fields
        (field (name "MANUFACTURER") "TDK Corporation")
        (field (name "MANUFACTURER PART NUMBER") "C0603X5R0J224M030BB")
        (field (name ".CHECKED PCB") "MM")
        (field (name ".CHECKED SCH") "MM")
        (field (name ".CREATOR") "MM")
      )
      (libsource (lib "Integrated_Library_FEDEVEL_0201") (part "C0603X5R0J224M030BB"))
    )
    (comp (ref "C56")
      (value "220n")
      (footprint "C0201")
      (description "CAP CER 0.22UF 6.3V 20% X5R 0201")
      (fields
        (field (name "MANUFACTURER") "TDK Corporation")
        (field (name "MANUFACTURER PART NUMBER") "C0603X5R0J224M030BB")
        (field (name ".CHECKED PCB") "MM")
        (field (name ".CHECKED SCH") "MM")
        (field (name ".CREATOR") "MM")
      )
      (libsource (lib "Integrated_Library_FEDEVEL_0201") (part "C0603X5R0J224M030BB"))
    )
    (comp (ref "C57")
      (value "220n")
      (footprint "C0201")
      (description "CAP CER 0.22UF 6.3V 20% X5R 0201")
      (fields
        (field (name "MANUFACTURER") "TDK Corporation")
        (field (name "MANUFACTURER PART NUMBER") "C0603X5R0J224M030BB")
        (field (name ".CHECKED PCB") "MM")
        (field (name ".CHECKED SCH") "MM")
        (field (name ".CREATOR") "MM")
      )
      (libsource (lib "Integrated_Library_FEDEVEL_0201") (part "C0603X5R0J224M030BB"))
    )
    (comp (ref "C58")
      (value "220n")
      (footprint "C0201")
      (description "CAP CER 0.22UF 6.3V 20% X5R 0201")
      (fields
        (field (name "MANUFACTURER") "TDK Corporation")
        (field (name "MANUFACTURER PART NUMBER") "C0603X5R0J224M030BB")
        (field (name ".CHECKED PCB") "MM")
        (field (name ".CHECKED SCH") "MM")
        (field (name ".CREATOR") "MM")
      )
      (libsource (lib "Integrated_Library_FEDEVEL_0201") (part "C0603X5R0J224M030BB"))
    )
    (comp (ref "C59")
      (value "220n")
      (footprint "C0201")
      (description "CAP CER 0.22UF 6.3V 20% X5R 0201")
      (fields
        (field (name "MANUFACTURER") "TDK Corporation")
        (field (name "MANUFACTURER PART NUMBER") "C0603X5R0J224M030BB")
        (field (name ".CHECKED PCB") "MM")
        (field (name ".CHECKED SCH") "MM")
        (field (name ".CREATOR") "MM")
      )
      (libsource (lib "Integrated_Library_FEDEVEL_0201") (part "C0603X5R0J224M030BB"))
    )
    (comp (ref "C60")
      (value "220n")
      (footprint "C0201")
      (description "CAP CER 0.22UF 6.3V 20% X5R 0201")
      (fields
        (field (name "MANUFACTURER") "TDK Corporation")
        (field (name "MANUFACTURER PART NUMBER") "C0603X5R0J224M030BB")
        (field (name ".CHECKED PCB") "MM")
        (field (name ".CHECKED SCH") "MM")
        (field (name ".CREATOR") "MM")
      )
      (libsource (lib "Integrated_Library_FEDEVEL_0201") (part "C0603X5R0J224M030BB"))
    )
    (comp (ref "C74")
      (value "100n")
      (footprint "C0201")
      (description "CAP CER 0.1UF 16V 10% X5R 0201")
      (fields
        (field (name "MANUFACTURER") "TDK Corporation")
        (field (name "MANUFACTURER PART NUMBER") "C0603X5R1C104K030BC")
        (field (name ".CREATOR") "MM")
        (field (name ".CHECKED PCB") "MM")
        (field (name ".CHECKED SCH") "MM")
      )
      (libsource (lib "Integrated_Library_FEDEVEL_0201") (part "C0603X5R1C104K030BC"))
    )
    (comp (ref "C85")
      (value "100n")
      (footprint "C0201")
      (description "CAP CER 0.1UF 16V 10% X5R 0201")
      (fields
        (field (name "MANUFACTURER") "TDK Corporation")
        (field (name "MANUFACTURER PART NUMBER") "C0603X5R1C104K030BC")
        (field (name ".CREATOR") "MM")
        (field (name ".CHECKED PCB") "MM")
        (field (name ".CHECKED SCH") "MM")
      )
      (libsource (lib "Integrated_Library_FEDEVEL_0201") (part "C0603X5R1C104K030BC"))
    )
    (comp (ref "C86")
      (value "100n")
      (footprint "C0201")
      (description "CAP CER 0.1UF 16V 10% X5R 0201")
      (fields
        (field (name "MANUFACTURER") "TDK Corporation")
        (field (name "MANUFACTURER PART NUMBER") "C0603X5R1C104K030BC")
        (field (name ".CREATOR") "MM")
        (field (name ".CHECKED PCB") "MM")
        (field (name ".CHECKED SCH") "MM")
      )
      (libsource (lib "Integrated_Library_FEDEVEL_0201") (part "C0603X5R1C104K030BC"))
    )
    (comp (ref "C203")
      (value "220n")
      (footprint "C0201")
      (description "CAP CER 0.22UF 6.3V 20% X5R 0201")
      (fields
        (field (name "MANUFACTURER") "TDK Corporation")
        (field (name "MANUFACTURER PART NUMBER") "C0603X5R0J224M030BB")
        (field (name ".CHECKED PCB") "MM")
        (field (name ".CHECKED SCH") "MM")
        (field (name ".CREATOR") "MM")
      )
      (libsource (lib "Integrated_Library_FEDEVEL_0201") (part "C0603X5R0J224M030BB"))
    )
    (comp (ref "C204")
      (value "220n")
      (footprint "C0201")
      (description "CAP CER 0.22UF 6.3V 20% X5R 0201")
      (fields
        (field (name "MANUFACTURER") "TDK Corporation")
        (field (name "MANUFACTURER PART NUMBER") "C0603X5R0J224M030BB")
        (field (name ".CHECKED PCB") "MM")
        (field (name ".CHECKED SCH") "MM")
        (field (name ".CREATOR") "MM")
      )
      (libsource (lib "Integrated_Library_FEDEVEL_0201") (part "C0603X5R0J224M030BB"))
    )
    (comp (ref "C205")
      (value "220n")
      (footprint "C0201")
      (description "CAP CER 0.22UF 6.3V 20% X5R 0201")
      (fields
        (field (name "MANUFACTURER") "TDK Corporation")
        (field (name "MANUFACTURER PART NUMBER") "C0603X5R0J224M030BB")
        (field (name ".CHECKED PCB") "MM")
        (field (name ".CHECKED SCH") "MM")
        (field (name ".CREATOR") "MM")
      )
      (libsource (lib "Integrated_Library_FEDEVEL_0201") (part "C0603X5R0J224M030BB"))
    )
    (comp (ref "C206")
      (value "100n")
      (footprint "C0201")
      (description "CAP CER 0.1UF 16V 10% X5R 0201")
      (fields
        (field (name "MANUFACTURER") "TDK Corporation")
        (field (name "MANUFACTURER PART NUMBER") "C0603X5R1C104K030BC")
        (field (name ".CREATOR") "MM")
        (field (name ".CHECKED PCB") "MM")
        (field (name ".CHECKED SCH") "MM")
      )
      (libsource (lib "Integrated_Library_FEDEVEL_0201") (part "C0603X5R1C104K030BC"))
    )
    (comp (ref "C229")
      (value "100n")
      (footprint "C0201")
      (description "CAP CER 0.1UF 16V 10% X5R 0201")
      (fields
        (field (name "MANUFACTURER") "TDK Corporation")
        (field (name "MANUFACTURER PART NUMBER") "C0603X5R1C104K030BC")
        (field (name ".CREATOR") "MM")
        (field (name ".CHECKED PCB") "MM")
        (field (name ".CHECKED SCH") "MM")
      )
      (libsource (lib "Integrated_Library_FEDEVEL_0201") (part "C0603X5R1C104K030BC"))
    )
    (comp (ref "C277")
      (value "100n")
      (footprint "C0201")
      (description "CAP CER 0.1UF 16V 10% X5R 0201")
      (fields
        (field (name "MANUFACTURER") "TDK Corporation")
        (field (name "MANUFACTURER PART NUMBER") "C0603X5R1C104K030BC")
        (field (name ".CREATOR") "MM")
        (field (name ".CHECKED PCB") "MM")
        (field (name ".CHECKED SCH") "MM")
      )
      (libsource (lib "Integrated_Library_FEDEVEL_0201") (part "C0603X5R1C104K030BC"))
    )
    (comp (ref "C297")
      (value "100n")
      (footprint "C0201")
      (description "CAP CER 0.1UF 16V 10% X5R 0201")
      (fields
        (field (name "MANUFACTURER") "TDK Corporation")
        (field (name "MANUFACTURER PART NUMBER") "C0603X5R1C104K030BC")
        (field (name ".CREATOR") "MM")
        (field (name ".CHECKED PCB") "MM")
        (field (name ".CHECKED SCH") "MM")
      )
      (libsource (lib "Integrated_Library_FEDEVEL_0201") (part "C0603X5R1C104K030BC"))
    )
    (comp (ref "C305")
      (value "100n")
      (footprint "C0201")
      (description "CAP CER 0.1UF 16V 10% X5R 0201")
      (fields
        (field (name "MANUFACTURER") "TDK Corporation")
        (field (name "MANUFACTURER PART NUMBER") "C0603X5R1C104K030BC")
        (field (name ".CREATOR") "MM")
        (field (name ".CHECKED PCB") "MM")
        (field (name ".CHECKED SCH") "MM")
      )
      (libsource (lib "Integrated_Library_FEDEVEL_0201") (part "C0603X5R1C104K030BC"))
    )
    (comp (ref "C306")
      (value "100n")
      (footprint "C0201")
      (description "CAP CER 0.1UF 16V 10% X5R 0201")
      (fields
        (field (name "MANUFACTURER") "TDK Corporation")
        (field (name "MANUFACTURER PART NUMBER") "C0603X5R1C104K030BC")
        (field (name ".CREATOR") "MM")
        (field (name ".CHECKED PCB") "MM")
        (field (name ".CHECKED SCH") "MM")
      )
      (libsource (lib "Integrated_Library_FEDEVEL_0201") (part "C0603X5R1C104K030BC"))
    )
    (comp (ref "C308")
      (value "100n")
      (footprint "C0201")
      (description "CAP CER 0.1UF 16V 10% X5R 0201")
      (fields
        (field (name "MANUFACTURER") "TDK Corporation")
        (field (name "MANUFACTURER PART NUMBER") "C0603X5R1C104K030BC")
        (field (name ".CREATOR") "MM")
        (field (name ".CHECKED PCB") "MM")
        (field (name ".CHECKED SCH") "MM")
      )
      (libsource (lib "Integrated_Library_FEDEVEL_0201") (part "C0603X5R1C104K030BC"))
    )
    (comp (ref "C317")
      (value "100n")
      (footprint "C0201")
      (description "CAP CER 0.1UF 16V 10% X5R 0201")
      (fields
        (field (name "MANUFACTURER") "TDK Corporation")
        (field (name "MANUFACTURER PART NUMBER") "C0603X5R1C104K030BC")
        (field (name ".CREATOR") "MM")
        (field (name ".CHECKED PCB") "MM")
        (field (name ".CHECKED SCH") "MM")
      )
      (libsource (lib "Integrated_Library_FEDEVEL_0201") (part "C0603X5R1C104K030BC"))
    )
    (comp (ref "C318")
      (value "100n")
      (footprint "C0201")
      (description "CAP CER 0.1UF 16V 10% X5R 0201")
      (fields
        (field (name "MANUFACTURER") "TDK Corporation")
        (field (name "MANUFACTURER PART NUMBER") "C0603X5R1C104K030BC")
        (field (name ".CREATOR") "MM")
        (field (name ".CHECKED PCB") "MM")
        (field (name ".CHECKED SCH") "MM")
      )
      (libsource (lib "Integrated_Library_FEDEVEL_0201") (part "C0603X5R1C104K030BC"))
    )
    (comp (ref "C319")
      (value "100n")
      (footprint "C0201")
      (description "CAP CER 0.1UF 16V 10% X5R 0201")
      (fields
        (field (name "MANUFACTURER") "TDK Corporation")
        (field (name "MANUFACTURER PART NUMBER") "C0603X5R1C104K030BC")
        (field (name ".CREATOR") "MM")
        (field (name ".CHECKED PCB") "MM")
        (field (name ".CHECKED SCH") "MM")
      )
      (libsource (lib "Integrated_Library_FEDEVEL_0201") (part "C0603X5R1C104K030BC"))
    )
    (comp (ref "C320")
      (value "100n")
      (footprint "C0201")
      (description "CAP CER 0.1UF 16V 10% X5R 0201")
      (fields
        (field (name "MANUFACTURER") "TDK Corporation")
        (field (name "MANUFACTURER PART NUMBER") "C0603X5R1C104K030BC")
        (field (name ".CREATOR") "MM")
        (field (name ".CHECKED PCB") "MM")
        (field (name ".CHECKED SCH") "MM")
      )
      (libsource (lib "Integrated_Library_FEDEVEL_0201") (part "C0603X5R1C104K030BC"))
    )
    (comp (ref "C321")
      (value "22u")
      (footprint "C0603")
      (description "CAP CER 22UF 4V 20% X5R 0603")
      (fields
        (field (name "MANUFACTURER") "Murata Electronics North America")
        (field (name "MANUFACTURER PART NUMBER") "GRM188R60G226MEA0L")
        (field (name ".CREATOR") "MM")
      )
      (libsource (lib "Integrated_Library_FEDEVEL_APR_2015") (part "GRM188R60G226MEA0L"))
    )
    (comp (ref "C322")
      (value "100n")
      (footprint "C0201")
      (description "CAP CER 0.1UF 16V 10% X5R 0201")
      (fields
        (field (name "MANUFACTURER") "TDK Corporation")
        (field (name "MANUFACTURER PART NUMBER") "C0603X5R1C104K030BC")
        (field (name ".CREATOR") "MM")
        (field (name ".CHECKED PCB") "MM")
        (field (name ".CHECKED SCH") "MM")
      )
      (libsource (lib "Integrated_Library_FEDEVEL_0201") (part "C0603X5R1C104K030BC"))
    )
    (comp (ref "C323")
      (value "100n")
      (footprint "C0201")
      (description "CAP CER 0.1UF 16V 10% X5R 0201")
      (fields
        (field (name "MANUFACTURER") "TDK Corporation")
        (field (name "MANUFACTURER PART NUMBER") "C0603X5R1C104K030BC")
        (field (name ".CREATOR") "MM")
        (field (name ".CHECKED PCB") "MM")
        (field (name ".CHECKED SCH") "MM")
      )
      (libsource (lib "Integrated_Library_FEDEVEL_0201") (part "C0603X5R1C104K030BC"))
    )
    (comp (ref "C327")
      (value "2p2")
      (footprint "C0201")
      (description "CAP CER 2.2PF 50V C0G 0201")
      (fields
        (field (name "MANUFACTURER") "TDK Corporation")
        (field (name "MANUFACTURER PART NUMBER") "C0603C0G1H2R2C030BA")
        (field (name ".CHECKED PCB") "MM")
        (field (name ".CHECKED SCH") "MM")
        (field (name ".CREATOR") "MM")
      )
      (libsource (lib "Integrated_Library_FEDEVEL_0201") (part "C0603C0G1H2R2C030BA"))
    )
    (comp (ref "C328")
      (value "2p2")
      (footprint "C0201")
      (description "CAP CER 2.2PF 50V C0G 0201")
      (fields
        (field (name "MANUFACTURER") "TDK Corporation")
        (field (name "MANUFACTURER PART NUMBER") "C0603C0G1H2R2C030BA")
        (field (name ".CHECKED PCB") "MM")
        (field (name ".CHECKED SCH") "MM")
        (field (name ".CREATOR") "MM")
      )
      (libsource (lib "Integrated_Library_FEDEVEL_0201") (part "C0603C0G1H2R2C030BA"))
    )
    (comp (ref "C392")
      (value "100n")
      (footprint "C0402")
      (description "CAP CER .10UF 50V X5R 10% 0402")
      (fields
        (field (name "MANUFACTURER") "TDK Corporation")
        (field (name "MANUFACTURER PART NUMBER") "C1005X5R1H104K")
      )
      (libsource (lib "Integrated_Library_FEDEVEL_APR_2015") (part "C1005X5R1H104K"))
    )
    (comp (ref "C393")
      (value "100n")
      (footprint "C0402")
      (description "CAP CER .10UF 50V X5R 10% 0402")
      (fields
        (field (name "MANUFACTURER") "TDK Corporation")
        (field (name "MANUFACTURER PART NUMBER") "C1005X5R1H104K")
      )
      (libsource (lib "Integrated_Library_FEDEVEL_APR_2015") (part "C1005X5R1H104K"))
    )
    (comp (ref "R1")
      (value "47R")
      (footprint "R0201")
      (description "RES SMD 47 OHM 1% 1/20W 0201")
      (fields
        (field (name "MANUFACTURER") "Rohm Semiconductor")
        (field (name "MANUFACTURER PART NUMBER") "MCR006YRTF47R0")
        (field (name ".CREATOR") "MM")
        (field (name ".CHECKED PCB") "MM")
        (field (name ".CHECKED SCH") "MM")
      )
      (libsource (lib "Integrated_Library_FEDEVEL_0201") (part "MCR006YRTF47R0"))
    )
    (comp (ref "R2")
      (value "47R")
      (footprint "R0201")
      (description "RES SMD 47 OHM 1% 1/20W 0201")
      (fields
        (field (name "MANUFACTURER") "Rohm Semiconductor")
        (field (name "MANUFACTURER PART NUMBER") "MCR006YRTF47R0")
        (field (name ".CREATOR") "MM")
        (field (name ".CHECKED PCB") "MM")
        (field (name ".CHECKED SCH") "MM")
      )
      (libsource (lib "Integrated_Library_FEDEVEL_0201") (part "MCR006YRTF47R0"))
    )
    (comp (ref "R3")
      (value "47R")
      (footprint "R0201")
      (description "RES SMD 47 OHM 1% 1/20W 0201")
      (fields
        (field (name "MANUFACTURER") "Rohm Semiconductor")
        (field (name "MANUFACTURER PART NUMBER") "MCR006YRTF47R0")
        (field (name ".CREATOR") "MM")
        (field (name ".CHECKED PCB") "MM")
        (field (name ".CHECKED SCH") "MM")
      )
      (libsource (lib "Integrated_Library_FEDEVEL_0201") (part "MCR006YRTF47R0"))
    )
    (comp (ref "R4")
      (value "240R")
      (footprint "R0201")
      (description "RES 240 OHM 1/20W 1% 0201")
      (fields
        (field (name "MANUFACTURER") "Stackpole Electronics Inc")
        (field (name "MANUFACTURER PART NUMBER") "RMCF0201FT240R")
        (field (name ".CREATOR") "MM")
        (field (name ".CHECKED PCB") "MM")
        (field (name ".CHECKED SCH") "MM")
      )
      (libsource (lib "Integrated_Library_FEDEVEL_0201") (part "RMCF0201FT240R"))
    )
    (comp (ref "R5")
      (value "240R")
      (footprint "R0201")
      (description "RES 240 OHM 1/20W 1% 0201")
      (fields
        (field (name "MANUFACTURER") "Stackpole Electronics Inc")
        (field (name "MANUFACTURER PART NUMBER") "RMCF0201FT240R")
        (field (name ".CREATOR") "MM")
        (field (name ".CHECKED PCB") "MM")
        (field (name ".CHECKED SCH") "MM")
      )
      (libsource (lib "Integrated_Library_FEDEVEL_0201") (part "RMCF0201FT240R"))
    )
    (comp (ref "R6")
      (value "10k")
      (footprint "R0201")
      (description "RES 10K OHM 1/20W 1% 0201 SMD")
      (fields
        (field (name "MANUFACTURER") "Yageo")
        (field (name "MANUFACTURER PART NUMBER") "RC0201FR-0710KL")
        (field (name ".CREATOR") "MM")
        (field (name ".CHECKED PCB") "MM")
        (field (name ".CHECKED SCH") "MM")
      )
      (libsource (lib "Integrated_Library_FEDEVEL_0201") (part "RC0201FR-0710KL"))
    )
    (comp (ref "R7")
      (value "10k")
      (footprint "R0201")
      (description "RES 10K OHM 1/20W 1% 0201 SMD")
      (fields
        (field (name "MANUFACTURER") "Yageo")
        (field (name "MANUFACTURER PART NUMBER") "RC0201FR-0710KL")
        (field (name ".CREATOR") "MM")
        (field (name ".CHECKED PCB") "MM")
        (field (name ".CHECKED SCH") "MM")
      )
      (libsource (lib "Integrated_Library_FEDEVEL_0201") (part "RC0201FR-0710KL"))
    )
    (comp (ref "R8")
      (value "240R")
      (footprint "R0201")
      (description "RES 240 OHM 1/20W 1% 0201")
      (fields
        (field (name "MANUFACTURER") "Stackpole Electronics Inc")
        (field (name "MANUFACTURER PART NUMBER") "RMCF0201FT240R")
        (field (name ".CREATOR") "MM")
        (field (name ".CHECKED PCB") "MM")
        (field (name ".CHECKED SCH") "MM")
      )
      (libsource (lib "Integrated_Library_FEDEVEL_0201") (part "RMCF0201FT240R"))
    )
    (comp (ref "R9")
      (value "240R")
      (footprint "R0201")
      (description "RES 240 OHM 1/20W 1% 0201")
      (fields
        (field (name "MANUFACTURER") "Stackpole Electronics Inc")
        (field (name "MANUFACTURER PART NUMBER") "RMCF0201FT240R")
        (field (name ".CREATOR") "MM")
        (field (name ".CHECKED PCB") "MM")
        (field (name ".CHECKED SCH") "MM")
      )
      (libsource (lib "Integrated_Library_FEDEVEL_0201") (part "RMCF0201FT240R"))
    )
    (comp (ref "R10")
      (value "240R")
      (footprint "R0201")
      (description "RES 240 OHM 1/20W 1% 0201")
      (fields
        (field (name "MANUFACTURER") "Stackpole Electronics Inc")
        (field (name "MANUFACTURER PART NUMBER") "RMCF0201FT240R")
        (field (name ".CREATOR") "MM")
        (field (name ".CHECKED PCB") "MM")
        (field (name ".CHECKED SCH") "MM")
      )
      (libsource (lib "Integrated_Library_FEDEVEL_0201") (part "RMCF0201FT240R"))
    )
    (comp (ref "R11")
      (value "47R")
      (footprint "R0201")
      (description "RES SMD 47 OHM 1% 1/20W 0201")
      (fields
        (field (name "MANUFACTURER") "Rohm Semiconductor")
        (field (name "MANUFACTURER PART NUMBER") "MCR006YRTF47R0")
        (field (name ".CREATOR") "MM")
        (field (name ".CHECKED PCB") "MM")
        (field (name ".CHECKED SCH") "MM")
      )
      (libsource (lib "Integrated_Library_FEDEVEL_0201") (part "MCR006YRTF47R0"))
    )
    (comp (ref "R12")
      (value "47R")
      (footprint "R0201")
      (description "RES SMD 47 OHM 1% 1/20W 0201")
      (fields
        (field (name "MANUFACTURER") "Rohm Semiconductor")
        (field (name "MANUFACTURER PART NUMBER") "MCR006YRTF47R0")
        (field (name ".CREATOR") "MM")
        (field (name ".CHECKED PCB") "MM")
        (field (name ".CHECKED SCH") "MM")
      )
      (libsource (lib "Integrated_Library_FEDEVEL_0201") (part "MCR006YRTF47R0"))
    )
    (comp (ref "R22")
      (value "47R")
      (footprint "R0201")
      (description "RES SMD 47 OHM 1% 1/20W 0201")
      (fields
        (field (name "MANUFACTURER") "Rohm Semiconductor")
        (field (name "MANUFACTURER PART NUMBER") "MCR006YRTF47R0")
        (field (name ".CREATOR") "MM")
        (field (name ".CHECKED PCB") "MM")
        (field (name ".CHECKED SCH") "MM")
      )
      (libsource (lib "Integrated_Library_FEDEVEL_0201") (part "MCR006YRTF47R0"))
    )
    (comp (ref "R31")
      (value "47R")
      (footprint "R0201")
      (description "RES SMD 47 OHM 1% 1/20W 0201")
      (fields
        (field (name "MANUFACTURER") "Rohm Semiconductor")
        (field (name "MANUFACTURER PART NUMBER") "MCR006YRTF47R0")
        (field (name ".CREATOR") "MM")
        (field (name ".CHECKED PCB") "MM")
        (field (name ".CHECKED SCH") "MM")
      )
      (libsource (lib "Integrated_Library_FEDEVEL_0201") (part "MCR006YRTF47R0"))
    )
    (comp (ref "R34")
      (value "47R")
      (footprint "R0201")
      (description "RES SMD 47 OHM 1% 1/20W 0201")
      (fields
        (field (name "MANUFACTURER") "Rohm Semiconductor")
        (field (name "MANUFACTURER PART NUMBER") "MCR006YRTF47R0")
        (field (name ".CREATOR") "MM")
        (field (name ".CHECKED PCB") "MM")
        (field (name ".CHECKED SCH") "MM")
      )
      (libsource (lib "Integrated_Library_FEDEVEL_0201") (part "MCR006YRTF47R0"))
    )
    (comp (ref "R38")
      (value "47R")
      (footprint "R0201")
      (description "RES SMD 47 OHM 1% 1/20W 0201")
      (fields
        (field (name "MANUFACTURER") "Rohm Semiconductor")
        (field (name "MANUFACTURER PART NUMBER") "MCR006YRTF47R0")
        (field (name ".CREATOR") "MM")
        (field (name ".CHECKED PCB") "MM")
        (field (name ".CHECKED SCH") "MM")
      )
      (libsource (lib "Integrated_Library_FEDEVEL_0201") (part "MCR006YRTF47R0"))
    )
    (comp (ref "R39")
      (value "47R")
      (footprint "R0201")
      (description "RES SMD 47 OHM 1% 1/20W 0201")
      (fields
        (field (name "MANUFACTURER") "Rohm Semiconductor")
        (field (name "MANUFACTURER PART NUMBER") "MCR006YRTF47R0")
        (field (name ".CREATOR") "MM")
        (field (name ".CHECKED PCB") "MM")
        (field (name ".CHECKED SCH") "MM")
      )
      (libsource (lib "Integrated_Library_FEDEVEL_0201") (part "MCR006YRTF47R0"))
    )
    (comp (ref "R40")
      (value "47R")
      (footprint "R0201")
      (description "RES SMD 47 OHM 1% 1/20W 0201")
      (fields
        (field (name "MANUFACTURER") "Rohm Semiconductor")
        (field (name "MANUFACTURER PART NUMBER") "MCR006YRTF47R0")
        (field (name ".CREATOR") "MM")
        (field (name ".CHECKED PCB") "MM")
        (field (name ".CHECKED SCH") "MM")
      )
      (libsource (lib "Integrated_Library_FEDEVEL_0201") (part "MCR006YRTF47R0"))
    )
    (comp (ref "R42")
      (value "47R")
      (footprint "R0201")
      (description "RES SMD 47 OHM 1% 1/20W 0201")
      (fields
        (field (name "MANUFACTURER") "Rohm Semiconductor")
        (field (name "MANUFACTURER PART NUMBER") "MCR006YRTF47R0")
        (field (name ".CREATOR") "MM")
        (field (name ".CHECKED PCB") "MM")
        (field (name ".CHECKED SCH") "MM")
      )
      (libsource (lib "Integrated_Library_FEDEVEL_0201") (part "MCR006YRTF47R0"))
    )
    (comp (ref "R44")
      (value "47R")
      (footprint "R0201")
      (description "RES SMD 47 OHM 1% 1/20W 0201")
      (fields
        (field (name "MANUFACTURER") "Rohm Semiconductor")
        (field (name "MANUFACTURER PART NUMBER") "MCR006YRTF47R0")
        (field (name ".CREATOR") "MM")
        (field (name ".CHECKED PCB") "MM")
        (field (name ".CHECKED SCH") "MM")
      )
      (libsource (lib "Integrated_Library_FEDEVEL_0201") (part "MCR006YRTF47R0"))
    )
    (comp (ref "R45")
      (value "47R")
      (footprint "R0201")
      (description "RES SMD 47 OHM 1% 1/20W 0201")
      (fields
        (field (name "MANUFACTURER") "Rohm Semiconductor")
        (field (name "MANUFACTURER PART NUMBER") "MCR006YRTF47R0")
        (field (name ".CREATOR") "MM")
        (field (name ".CHECKED PCB") "MM")
        (field (name ".CHECKED SCH") "MM")
      )
      (libsource (lib "Integrated_Library_FEDEVEL_0201") (part "MCR006YRTF47R0"))
    )
    (comp (ref "R50")
      (value "47R")
      (footprint "R0201")
      (description "RES SMD 47 OHM 1% 1/20W 0201")
      (fields
        (field (name "MANUFACTURER") "Rohm Semiconductor")
        (field (name "MANUFACTURER PART NUMBER") "MCR006YRTF47R0")
        (field (name ".CREATOR") "MM")
        (field (name ".CHECKED PCB") "MM")
        (field (name ".CHECKED SCH") "MM")
      )
      (libsource (lib "Integrated_Library_FEDEVEL_0201") (part "MCR006YRTF47R0"))
    )
    (comp (ref "R66")
      (value "47R")
      (footprint "R0201")
      (description "RES SMD 47 OHM 1% 1/20W 0201")
      (fields
        (field (name "MANUFACTURER") "Rohm Semiconductor")
        (field (name "MANUFACTURER PART NUMBER") "MCR006YRTF47R0")
        (field (name ".CREATOR") "MM")
        (field (name ".CHECKED PCB") "MM")
        (field (name ".CHECKED SCH") "MM")
      )
      (libsource (lib "Integrated_Library_FEDEVEL_0201") (part "MCR006YRTF47R0"))
    )
    (comp (ref "R72")
      (value "47R")
      (footprint "R0201")
      (description "RES SMD 47 OHM 1% 1/20W 0201")
      (fields
        (field (name "MANUFACTURER") "Rohm Semiconductor")
        (field (name "MANUFACTURER PART NUMBER") "MCR006YRTF47R0")
        (field (name ".CREATOR") "MM")
        (field (name ".CHECKED PCB") "MM")
        (field (name ".CHECKED SCH") "MM")
      )
      (libsource (lib "Integrated_Library_FEDEVEL_0201") (part "MCR006YRTF47R0"))
    )
    (comp (ref "R77")
      (value "47R")
      (footprint "R0201")
      (description "RES SMD 47 OHM 1% 1/20W 0201")
      (fields
        (field (name "MANUFACTURER") "Rohm Semiconductor")
        (field (name "MANUFACTURER PART NUMBER") "MCR006YRTF47R0")
        (field (name ".CREATOR") "MM")
        (field (name ".CHECKED PCB") "MM")
        (field (name ".CHECKED SCH") "MM")
      )
      (libsource (lib "Integrated_Library_FEDEVEL_0201") (part "MCR006YRTF47R0"))
    )
    (comp (ref "R79")
      (value "47R")
      (footprint "R0201")
      (description "RES SMD 47 OHM 1% 1/20W 0201")
      (fields
        (field (name "MANUFACTURER") "Rohm Semiconductor")
        (field (name "MANUFACTURER PART NUMBER") "MCR006YRTF47R0")
        (field (name ".CREATOR") "MM")
        (field (name ".CHECKED PCB") "MM")
        (field (name ".CHECKED SCH") "MM")
      )
      (libsource (lib "Integrated_Library_FEDEVEL_0201") (part "MCR006YRTF47R0"))
    )
    (comp (ref "R103")
      (value "47R")
      (footprint "R0201")
      (description "RES SMD 47 OHM 1% 1/20W 0201")
      (fields
        (field (name "MANUFACTURER") "Rohm Semiconductor")
        (field (name "MANUFACTURER PART NUMBER") "MCR006YRTF47R0")
        (field (name ".CREATOR") "MM")
        (field (name ".CHECKED PCB") "MM")
        (field (name ".CHECKED SCH") "MM")
      )
      (libsource (lib "Integrated_Library_FEDEVEL_0201") (part "MCR006YRTF47R0"))
    )
    (comp (ref "R105")
      (value "47R")
      (footprint "R0201")
      (description "RES SMD 47 OHM 1% 1/20W 0201")
      (fields
        (field (name "MANUFACTURER") "Rohm Semiconductor")
        (field (name "MANUFACTURER PART NUMBER") "MCR006YRTF47R0")
        (field (name ".CREATOR") "MM")
        (field (name ".CHECKED PCB") "MM")
        (field (name ".CHECKED SCH") "MM")
      )
      (libsource (lib "Integrated_Library_FEDEVEL_0201") (part "MCR006YRTF47R0"))
    )
    (comp (ref "R106")
      (value "47R")
      (footprint "R0201")
      (description "RES SMD 47 OHM 1% 1/20W 0201")
      (fields
        (field (name "MANUFACTURER") "Rohm Semiconductor")
        (field (name "MANUFACTURER PART NUMBER") "MCR006YRTF47R0")
        (field (name ".CREATOR") "MM")
        (field (name ".CHECKED PCB") "MM")
        (field (name ".CHECKED SCH") "MM")
      )
      (libsource (lib "Integrated_Library_FEDEVEL_0201") (part "MCR006YRTF47R0"))
    )
    (comp (ref "R107")
      (value "47R")
      (footprint "R0201")
      (description "RES SMD 47 OHM 1% 1/20W 0201")
      (fields
        (field (name "MANUFACTURER") "Rohm Semiconductor")
        (field (name "MANUFACTURER PART NUMBER") "MCR006YRTF47R0")
        (field (name ".CREATOR") "MM")
        (field (name ".CHECKED PCB") "MM")
        (field (name ".CHECKED SCH") "MM")
      )
      (libsource (lib "Integrated_Library_FEDEVEL_0201") (part "MCR006YRTF47R0"))
    )
    (comp (ref "R108")
      (value "47R")
      (footprint "R0201")
      (description "RES SMD 47 OHM 1% 1/20W 0201")
      (fields
        (field (name "MANUFACTURER") "Rohm Semiconductor")
        (field (name "MANUFACTURER PART NUMBER") "MCR006YRTF47R0")
        (field (name ".CREATOR") "MM")
        (field (name ".CHECKED PCB") "MM")
        (field (name ".CHECKED SCH") "MM")
      )
      (libsource (lib "Integrated_Library_FEDEVEL_0201") (part "MCR006YRTF47R0"))
    )
    (comp (ref "R111")
      (value "47R")
      (footprint "R0201")
      (description "RES SMD 47 OHM 1% 1/20W 0201")
      (fields
        (field (name "MANUFACTURER") "Rohm Semiconductor")
        (field (name "MANUFACTURER PART NUMBER") "MCR006YRTF47R0")
        (field (name ".CREATOR") "MM")
        (field (name ".CHECKED PCB") "MM")
        (field (name ".CHECKED SCH") "MM")
      )
      (libsource (lib "Integrated_Library_FEDEVEL_0201") (part "MCR006YRTF47R0"))
    )
    (comp (ref "R112")
      (value "49R9")
      (footprint "R0201")
      (description "RES 49.9 OHM 1/20W 1% 0201 SMD")
      (fields
        (field (name "MANUFACTURER") "Rohm Semiconductor")
        (field (name "MANUFACTURER PART NUMBER") "MCR006YRTF49R9")
        (field (name ".CREATOR") "MM")
        (field (name ".CHECKED PCB") "MM")
        (field (name ".CHECKED SCH") "MM")
      )
      (libsource (lib "Integrated_Library_FEDEVEL_0201") (part "MCR006YRTF49R9"))
    )
    (comp (ref "R113")
      (value "49R9")
      (footprint "R0201")
      (description "RES 49.9 OHM 1/20W 1% 0201 SMD")
      (fields
        (field (name "MANUFACTURER") "Rohm Semiconductor")
        (field (name "MANUFACTURER PART NUMBER") "MCR006YRTF49R9")
        (field (name ".CREATOR") "MM")
        (field (name ".CHECKED PCB") "MM")
        (field (name ".CHECKED SCH") "MM")
      )
      (libsource (lib "Integrated_Library_FEDEVEL_0201") (part "MCR006YRTF49R9"))
    )
    (comp (ref "R245")
      (value "240R")
      (footprint "R0402")
      (description "RES TF 240 OHM 1% 0.0625W 0402")
      (fields
        (field (name "MANUFACTURER") "Stackpole Electronics Inc")
        (field (name "MANUFACTURER PART NUMBER") "RMCF0402FT240R")
      )
      (libsource (lib "Integrated_Library_FEDEVEL_APR_2015") (part "RMCF0402FT240R"))
    )
    (comp (ref "R253")
      (value "49R9")
      (footprint "R0201")
      (description "RES 49.9 OHM 1/20W 1% 0201 SMD")
      (fields
        (field (name "MANUFACTURER") "Rohm Semiconductor")
        (field (name "MANUFACTURER PART NUMBER") "MCR006YRTF49R9")
        (field (name ".CREATOR") "MM")
        (field (name ".CHECKED PCB") "MM")
        (field (name ".CHECKED SCH") "MM")
      )
      (libsource (lib "Integrated_Library_FEDEVEL_0201") (part "MCR006YRTF49R9"))
    )
    (comp (ref "R256")
      (value "49R9")
      (footprint "R0201")
      (description "RES 49.9 OHM 1/20W 1% 0201 SMD")
      (fields
        (field (name "MANUFACTURER") "Rohm Semiconductor")
        (field (name "MANUFACTURER PART NUMBER") "MCR006YRTF49R9")
        (field (name ".CREATOR") "MM")
        (field (name ".CHECKED PCB") "MM")
        (field (name ".CHECKED SCH") "MM")
      )
      (libsource (lib "Integrated_Library_FEDEVEL_0201") (part "MCR006YRTF49R9"))
    )
    (comp (ref "R274")
      (value "240R")
      (footprint "R0402")
      (description "RES TF 240 OHM 1% 0.0625W 0402")
      (fields
        (field (name "MANUFACTURER") "Stackpole Electronics Inc")
        (field (name "MANUFACTURER PART NUMBER") "RMCF0402FT240R")
      )
      (libsource (lib "Integrated_Library_FEDEVEL_APR_2015") (part "RMCF0402FT240R"))
    )
    (comp (ref "R306")
      (value "240R")
      (footprint "R0201")
      (description "RES 240 OHM 1/20W 1% 0201")
      (fields
        (field (name "MANUFACTURER") "Stackpole Electronics Inc")
        (field (name "MANUFACTURER PART NUMBER") "RMCF0201FT240R")
        (field (name ".CREATOR") "MM")
        (field (name ".CHECKED PCB") "MM")
        (field (name ".CHECKED SCH") "MM")
      )
      (libsource (lib "Integrated_Library_FEDEVEL_0201") (part "RMCF0201FT240R"))
    )
    (comp (ref "R307")
      (value "240R")
      (footprint "R0201")
      (description "RES 240 OHM 1/20W 1% 0201")
      (fields
        (field (name "MANUFACTURER") "Stackpole Electronics Inc")
        (field (name "MANUFACTURER PART NUMBER") "RMCF0201FT240R")
        (field (name ".CREATOR") "MM")
        (field (name ".CHECKED PCB") "MM")
        (field (name ".CHECKED SCH") "MM")
      )
      (libsource (lib "Integrated_Library_FEDEVEL_0201") (part "RMCF0201FT240R"))
    )
    (comp (ref "R308")
      (value "240R")
      (footprint "R0201")
      (description "RES 240 OHM 1/20W 1% 0201")
      (fields
        (field (name "MANUFACTURER") "Stackpole Electronics Inc")
        (field (name "MANUFACTURER PART NUMBER") "RMCF0201FT240R")
        (field (name ".CREATOR") "MM")
        (field (name ".CHECKED PCB") "MM")
        (field (name ".CHECKED SCH") "MM")
      )
      (libsource (lib "Integrated_Library_FEDEVEL_0201") (part "RMCF0201FT240R"))
    )
    (comp (ref "R309")
      (value "240R")
      (footprint "R0201")
      (description "RES 240 OHM 1/20W 1% 0201")
      (fields
        (field (name "MANUFACTURER") "Stackpole Electronics Inc")
        (field (name "MANUFACTURER PART NUMBER") "RMCF0201FT240R")
        (field (name ".CREATOR") "MM")
        (field (name ".CHECKED PCB") "MM")
        (field (name ".CHECKED SCH") "MM")
      )
      (libsource (lib "Integrated_Library_FEDEVEL_0201") (part "RMCF0201FT240R"))
    )
    (comp (ref "U1")
      (value "MCIMX6Q5EYM10AC_v.ORX")
      (footprint "PBGA624")
      (description "IC MCU 32BIT ARM QUAD 624FCBGA")
      (fields
        (field (name "MANUFACTURER") "Freescale Semiconductor")
        (field (name "MANUFACTURER PART NUMBER") "MCIMX6Q5EYM10AC")
        (field (name ".CREATOR") "MM")
        (field (name ".CHECKED PCB") "MM, checked by RF")
      )
      (libsource (lib "Integrated_Library_FEDEVEL_APR_2015") (part "MCIMX6Q5EYM10AC_v.ORX"))
    )
    (comp (ref "U2")
      (value "MT41J256M16HA-125:E")
      (footprint "96_FPGA_DD3_14mmx10mm-small_size")
      (description "IC DDR3 SDRAM 4GBIT 800MHZ FBGA")
      (fields
        (field (name "MANUFACTURER") "Micron Technology Inc")
        (field (name ".CREATOR") "MM")
        (field (name ".CHECKED PCB") "MM")
        (field (name ".CHECKED SCH") "MM")
      )
      (libsource (lib "Integrated_Library_FEDEVEL_APR_2015") (part "MT41J256M16HA-125{colon}E"))
    )
    (comp (ref "U3")
      (value "MT41J256M16HA-125:E")
      (footprint "96_FPGA_DD3_14mmx10mm-small_size")
      (description "IC DDR3 SDRAM 4GBIT 800MHZ FBGA")
      (fields
        (field (name "MANUFACTURER") "Micron Technology Inc")
        (field (name ".CREATOR") "MM")
        (field (name ".CHECKED PCB") "MM")
        (field (name ".CHECKED SCH") "MM")
      )
      (libsource (lib "Integrated_Library_FEDEVEL_APR_2015") (part "MT41J256M16HA-125{colon}E"))
    )
    (comp (ref "U4")
      (value "MT41J256M16HA-125:E")
      (footprint "96_FPGA_DD3_14mmx10mm-small_size")
      (description "IC DDR3 SDRAM 4GBIT 800MHZ FBGA")
      (fields
        (field (name "MANUFACTURER") "Micron Technology Inc")
        (field (name ".CREATOR") "MM")
        (field (name ".CHECKED PCB") "MM")
        (field (name ".CHECKED SCH") "MM")
      )
      (libsource (lib "Integrated_Library_FEDEVEL_APR_2015") (part "MT41J256M16HA-125{colon}E"))
    )
    (comp (ref "U5")
      (value "MT41J256M16HA-125:E")
      (footprint "96_FPGA_DD3_14mmx10mm-small_size")
      (description "IC DDR3 SDRAM 4GBIT 800MHZ FBGA")
      (fields
        (field (name "MANUFACTURER") "Micron Technology Inc")
        (field (name ".CREATOR") "MM")
        (field (name ".CHECKED PCB") "MM")
        (field (name ".CHECKED SCH") "MM")
      )
      (libsource (lib "Integrated_Library_FEDEVEL_APR_2015") (part "MT41J256M16HA-125{colon}E"))
    )
  )
  (nets
    (net (code "1") (name "+0V75_DDR_VTT") (class "Default")
      (node (ref "C13") (pin "2") (pinfunction "2_2") (pintype "passive"))
      (node (ref "C14") (pin "2") (pinfunction "2_2") (pintype "passive"))
      (node (ref "C15") (pin "2") (pinfunction "2_2") (pintype "passive"))
      (node (ref "C16") (pin "2") (pinfunction "2_2") (pintype "passive"))
      (node (ref "C17") (pin "2") (pinfunction "2_2") (pintype "passive"))
      (node (ref "C18") (pin "2") (pinfunction "2_2") (pintype "passive"))
      (node (ref "C20") (pin "2") (pinfunction "2_2") (pintype "passive"))
      (node (ref "C206") (pin "2") (pinfunction "2_2") (pintype "passive"))
      (node (ref "C229") (pin "1") (pinfunction "1_1") (pintype "passive"))
      (node (ref "C277") (pin "1") (pinfunction "1_1") (pintype "passive"))
      (node (ref "C297") (pin "1") (pinfunction "1_1") (pintype "passive"))
      (node (ref "C305") (pin "1") (pinfunction "1_1") (pintype "passive"))
      (node (ref "C306") (pin "1") (pinfunction "1_1") (pintype "passive"))
      (node (ref "C308") (pin "1") (pinfunction "1_1") (pintype "passive"))
      (node (ref "C317") (pin "1") (pinfunction "1_1") (pintype "passive"))
      (node (ref "C318") (pin "1") (pinfunction "1_1") (pintype "passive"))
      (node (ref "C319") (pin "1") (pinfunction "1_1") (pintype "passive"))
      (node (ref "C320") (pin "1") (pinfunction "1_1") (pintype "passive"))
      (node (ref "C321") (pin "1") (pinfunction "1_1") (pintype "passive"))
      (node (ref "C74") (pin "2") (pinfunction "2_2") (pintype "passive"))
      (node (ref "C85") (pin "2") (pinfunction "2_2") (pintype "passive"))
      (node (ref "C86") (pin "2") (pinfunction "2_2") (pintype "passive"))
      (node (ref "R1") (pin "2") (pinfunction "2_2") (pintype "passive"))
      (node (ref "R103") (pin "2") (pinfunction "2_2") (pintype "passive"))
      (node (ref "R105") (pin "2") (pinfunction "2_2") (pintype "passive"))
      (node (ref "R106") (pin "2") (pinfunction "2_2") (pintype "passive"))
      (node (ref "R107") (pin "2") (pinfunction "2_2") (pintype "passive"))
      (node (ref "R108") (pin "2") (pinfunction "2_2") (pintype "passive"))
      (node (ref "R11") (pin "2") (pinfunction "2_2") (pintype "passive"))
      (node (ref "R111") (pin "2") (pinfunction "2_2") (pintype "passive"))
      (node (ref "R12") (pin "2") (pinfunction "2_2") (pintype "passive"))
      (node (ref "R2") (pin "2") (pinfunction "2_2") (pintype "passive"))
      (node (ref "R22") (pin "2") (pinfunction "2_2") (pintype "passive"))
      (node (ref "R3") (pin "2") (pinfunction "2_2") (pintype "passive"))
      (node (ref "R31") (pin "2") (pinfunction "2_2") (pintype "passive"))
      (node (ref "R34") (pin "2") (pinfunction "2_2") (pintype "passive"))
      (node (ref "R38") (pin "2") (pinfunction "2_2") (pintype "passive"))
      (node (ref "R39") (pin "2") (pinfunction "2_2") (pintype "passive"))
      (node (ref "R40") (pin "2") (pinfunction "2_2") (pintype "passive"))
      (node (ref "R42") (pin "2") (pinfunction "2_2") (pintype "passive"))
      (node (ref "R44") (pin "2") (pinfunction "2_2") (pintype "passive"))
      (node (ref "R45") (pin "2") (pinfunction "2_2") (pintype "passive"))
      (node (ref "R50") (pin "2") (pinfunction "2_2") (pintype "passive"))
      (node (ref "R66") (pin "2") (pinfunction "2_2") (pintype "passive"))
      (node (ref "R72") (pin "2") (pinfunction "2_2") (pintype "passive"))
      (node (ref "R77") (pin "2") (pinfunction "2_2") (pintype "passive"))
      (node (ref "R79") (pin "2") (pinfunction "2_2") (pintype "passive"))
    )
    (net (code "2") (name "+1V5_DDR") (class "Default")
      (node (ref "C1") (pin "1") (pinfunction "1_1") (pintype "passive"))
      (node (ref "C12") (pin "1") (pinfunction "1_1") (pintype "passive"))
      (node (ref "C13") (pin "1") (pinfunction "1_1") (pintype "passive"))
      (node (ref "C14") (pin "1") (pinfunction "1_1") (pintype "passive"))
      (node (ref "C15") (pin "1") (pinfunction "1_1") (pintype "passive"))
      (node (ref "C16") (pin "1") (pinfunction "1_1") (pintype "passive"))
      (node (ref "C17") (pin "1") (pinfunction "1_1") (pintype "passive"))
      (node (ref "C18") (pin "1") (pinfunction "1_1") (pintype "passive"))
      (node (ref "C19") (pin "1") (pinfunction "1_1") (pintype "passive"))
      (node (ref "C2") (pin "1") (pinfunction "1_1") (pintype "passive"))
      (node (ref "C20") (pin "1") (pinfunction "1_1") (pintype "passive"))
      (node (ref "C203") (pin "1") (pinfunction "1_1") (pintype "passive"))
      (node (ref "C204") (pin "1") (pinfunction "1_1") (pintype "passive"))
      (node (ref "C205") (pin "1") (pinfunction "1_1") (pintype "passive"))
      (node (ref "C206") (pin "1") (pinfunction "1_1") (pintype "passive"))
      (node (ref "C21") (pin "1") (pinfunction "1_1") (pintype "passive"))
      (node (ref "C22") (pin "1") (pinfunction "1_1") (pintype "passive"))
      (node (ref "C23") (pin "1") (pinfunction "1_1") (pintype "passive"))
      (node (ref "C24") (pin "1") (pinfunction "1_1") (pintype "passive"))
      (node (ref "C25") (pin "1") (pinfunction "1_1") (pintype "passive"))
      (node (ref "C26") (pin "1") (pinfunction "1_1") (pintype "passive"))
      (node (ref "C27") (pin "1") (pinfunction "1_1") (pintype "passive"))
      (node (ref "C28") (pin "1") (pinfunction "1_1") (pintype "passive"))
      (node (ref "C29") (pin "1") (pinfunction "1_1") (pintype "passive"))
      (node (ref "C30") (pin "1") (pinfunction "1_1") (pintype "passive"))
      (node (ref "C31") (pin "1") (pinfunction "1_1") (pintype "passive"))
      (node (ref "C32") (pin "1") (pinfunction "1_1") (pintype "passive"))
      (node (ref "C322") (pin "2") (pinfunction "2_2") (pintype "passive"))
      (node (ref "C323") (pin "2") (pinfunction "2_2") (pintype "passive"))
      (node (ref "C33") (pin "1") (pinfunction "1_1") (pintype "passive"))
      (node (ref "C34") (pin "1") (pinfunction "1_1") (pintype "passive"))
      (node (ref "C35") (pin "1") (pinfunction "1_1") (pintype "passive"))
      (node (ref "C36") (pin "1") (pinfunction "1_1") (pintype "passive"))
      (node (ref "C37") (pin "1") (pinfunction "1_1") (pintype "passive"))
      (node (ref "C38") (pin "1") (pinfunction "1_1") (pintype "passive"))
      (node (ref "C39") (pin "1") (pinfunction "1_1") (pintype "passive"))
      (node (ref "C392") (pin "1") (pinfunction "1_1") (pintype "passive"))
      (node (ref "C40") (pin "1") (pinfunction "1_1") (pintype "passive"))
      (node (ref "C41") (pin "1") (pinfunction "1_1") (pintype "passive"))
      (node (ref "C42") (pin "1") (pinfunction "1_1") (pintype "passive"))
      (node (ref "C43") (pin "1") (pinfunction "1_1") (pintype "passive"))
      (node (ref "C44") (pin "1") (pinfunction "1_1") (pintype "passive"))
      (node (ref "C45") (pin "1") (pinfunction "1_1") (pintype "passive"))
      (node (ref "C46") (pin "1") (pinfunction "1_1") (pintype "passive"))
      (node (ref "C47") (pin "1") (pinfunction "1_1") (pintype "passive"))
      (node (ref "C48") (pin "1") (pinfunction "1_1") (pintype "passive"))
      (node (ref "C49") (pin "1") (pinfunction "1_1") (pintype "passive"))
      (node (ref "C50") (pin "1") (pinfunction "1_1") (pintype "passive"))
      (node (ref "C51") (pin "1") (pinfunction "1_1") (pintype "passive"))
      (node (ref "C52") (pin "1") (pinfunction "1_1") (pintype "passive"))
      (node (ref "C53") (pin "1") (pinfunction "1_1") (pintype "passive"))
      (node (ref "C54") (pin "1") (pinfunction "1_1") (pintype "passive"))
      (node (ref "C55") (pin "1") (pinfunction "1_1") (pintype "passive"))
      (node (ref "C56") (pin "1") (pinfunction "1_1") (pintype "passive"))
      (node (ref "C57") (pin "1") (pinfunction "1_1") (pintype "passive"))
      (node (ref "C58") (pin "1") (pinfunction "1_1") (pintype "passive"))
      (node (ref "C59") (pin "1") (pinfunction "1_1") (pintype "passive"))
      (node (ref "C60") (pin "1") (pinfunction "1_1") (pintype "passive"))
      (node (ref "C74") (pin "1") (pinfunction "1_1") (pintype "passive"))
      (node (ref "C85") (pin "1") (pinfunction "1_1") (pintype "passive"))
      (node (ref "C86") (pin "1") (pinfunction "1_1") (pintype "passive"))
      (node (ref "R245") (pin "2") (pinfunction "2_2") (pintype "passive"))
      (node (ref "U1") (pin "R18") (pinfunction "NVCC_DRAM_1_R18") (pintype "power_in"))
      (node (ref "U1") (pin "T18") (pinfunction "NVCC_DRAM_2_T18") (pintype "power_in"))
      (node (ref "U1") (pin "U18") (pinfunction "NVCC_DRAM_3_U18") (pintype "power_in"))
      (node (ref "U1") (pin "V10") (pinfunction "NVCC_DRAM_4_V10") (pintype "power_in"))
      (node (ref "U1") (pin "V11") (pinfunction "NVCC_DRAM_5_V11") (pintype "power_in"))
      (node (ref "U1") (pin "V12") (pinfunction "NVCC_DRAM_6_V12") (pintype "power_in"))
      (node (ref "U1") (pin "V13") (pinfunction "NVCC_DRAM_7_V13") (pintype "power_in"))
      (node (ref "U1") (pin "V14") (pinfunction "NVCC_DRAM_8_V14") (pintype "power_in"))
      (node (ref "U1") (pin "V15") (pinfunction "NVCC_DRAM_9_V15") (pintype "power_in"))
      (node (ref "U1") (pin "V16") (pinfunction "NVCC_DRAM_10_V16") (pintype "power_in"))
      (node (ref "U1") (pin "V17") (pinfunction "NVCC_DRAM_11_V17") (pintype "power_in"))
      (node (ref "U1") (pin "V18") (pinfunction "NVCC_DRAM_12_V18") (pintype "power_in"))
      (node (ref "U1") (pin "V9") (pinfunction "NVCC_DRAM_13_V9") (pintype "power_in"))
      (node (ref "U2") (pin "A1") (pinfunction "VDDQ1_A1") (pintype "power_in"))
      (node (ref "U2") (pin "A8") (pinfunction "VDDQ2_A8") (pintype "power_in"))
      (node (ref "U2") (pin "B2") (pinfunction "VDD1_B2") (pintype "power_in"))
      (node (ref "U2") (pin "C1") (pinfunction "VDDQ3_C1") (pintype "power_in"))
      (node (ref "U2") (pin "C9") (pinfunction "VDDQ4_C9") (pintype "power_in"))
      (node (ref "U2") (pin "D2") (pinfunction "VDDQ5_D2") (pintype "power_in"))
      (node (ref "U2") (pin "D9") (pinfunction "VDD2_D9") (pintype "power_in"))
      (node (ref "U2") (pin "E9") (pinfunction "VDDQ6_E9") (pintype "power_in"))
      (node (ref "U2") (pin "F1") (pinfunction "VDDQ7_F1") (pintype "power_in"))
      (node (ref "U2") (pin "G7") (pinfunction "VDD3_G7") (pintype "power_in"))
      (node (ref "U2") (pin "H2") (pinfunction "VDDQ8_H2") (pintype "power_in"))
      (node (ref "U2") (pin "H9") (pinfunction "VDDQ9_H9") (pintype "power_in"))
      (node (ref "U2") (pin "K2") (pinfunction "VDD4_K2") (pintype "power_in"))
      (node (ref "U2") (pin "K8") (pinfunction "VDD5_K8") (pintype "power_in"))
      (node (ref "U2") (pin "N1") (pinfunction "VDD6_N1") (pintype "power_in"))
      (node (ref "U2") (pin "N9") (pinfunction "VDD7_N9") (pintype "power_in"))
      (node (ref "U2") (pin "R1") (pinfunction "VDD8_R1") (pintype "power_in"))
      (node (ref "U2") (pin "R9") (pinfunction "VDD9_R9") (pintype "power_in"))
      (node (ref "U3") (pin "A1") (pinfunction "VDDQ1_A1") (pintype "power_in"))
      (node (ref "U3") (pin "A8") (pinfunction "VDDQ2_A8") (pintype "power_in"))
      (node (ref "U3") (pin "B2") (pinfunction "VDD1_B2") (pintype "power_in"))
      (node (ref "U3") (pin "C1") (pinfunction "VDDQ3_C1") (pintype "power_in"))
      (node (ref "U3") (pin "C9") (pinfunction "VDDQ4_C9") (pintype "power_in"))
      (node (ref "U3") (pin "D2") (pinfunction "VDDQ5_D2") (pintype "power_in"))
      (node (ref "U3") (pin "D9") (pinfunction "VDD2_D9") (pintype "power_in"))
      (node (ref "U3") (pin "E9") (pinfunction "VDDQ6_E9") (pintype "power_in"))
      (node (ref "U3") (pin "F1") (pinfunction "VDDQ7_F1") (pintype "power_in"))
      (node (ref "U3") (pin "G7") (pinfunction "VDD3_G7") (pintype "power_in"))
      (node (ref "U3") (pin "H2") (pinfunction "VDDQ8_H2") (pintype "power_in"))
      (node (ref "U3") (pin "H9") (pinfunction "VDDQ9_H9") (pintype "power_in"))
      (node (ref "U3") (pin "K2") (pinfunction "VDD4_K2") (pintype "power_in"))
      (node (ref "U3") (pin "K8") (pinfunction "VDD5_K8") (pintype "power_in"))
      (node (ref "U3") (pin "N1") (pinfunction "VDD6_N1") (pintype "power_in"))
      (node (ref "U3") (pin "N9") (pinfunction "VDD7_N9") (pintype "power_in"))
      (node (ref "U3") (pin "R1") (pinfunction "VDD8_R1") (pintype "power_in"))
      (node (ref "U3") (pin "R9") (pinfunction "VDD9_R9") (pintype "power_in"))
      (node (ref "U4") (pin "A1") (pinfunction "VDDQ1_A1") (pintype "power_in"))
      (node (ref "U4") (pin "A8") (pinfunction "VDDQ2_A8") (pintype "power_in"))
      (node (ref "U4") (pin "B2") (pinfunction "VDD1_B2") (pintype "power_in"))
      (node (ref "U4") (pin "C1") (pinfunction "VDDQ3_C1") (pintype "power_in"))
      (node (ref "U4") (pin "C9") (pinfunction "VDDQ4_C9") (pintype "power_in"))
      (node (ref "U4") (pin "D2") (pinfunction "VDDQ5_D2") (pintype "power_in"))
      (node (ref "U4") (pin "D9") (pinfunction "VDD2_D9") (pintype "power_in"))
      (node (ref "U4") (pin "E9") (pinfunction "VDDQ6_E9") (pintype "power_in"))
      (node (ref "U4") (pin "F1") (pinfunction "VDDQ7_F1") (pintype "power_in"))
      (node (ref "U4") (pin "G7") (pinfunction "VDD3_G7") (pintype "power_in"))
      (node (ref "U4") (pin "H2") (pinfunction "VDDQ8_H2") (pintype "power_in"))
      (node (ref "U4") (pin "H9") (pinfunction "VDDQ9_H9") (pintype "power_in"))
      (node (ref "U4") (pin "K2") (pinfunction "VDD4_K2") (pintype "power_in"))
      (node (ref "U4") (pin "K8") (pinfunction "VDD5_K8") (pintype "power_in"))
      (node (ref "U4") (pin "N1") (pinfunction "VDD6_N1") (pintype "power_in"))
      (node (ref "U4") (pin "N9") (pinfunction "VDD7_N9") (pintype "power_in"))
      (node (ref "U4") (pin "R1") (pinfunction "VDD8_R1") (pintype "power_in"))
      (node (ref "U4") (pin "R9") (pinfunction "VDD9_R9") (pintype "power_in"))
      (node (ref "U5") (pin "A1") (pinfunction "VDDQ1_A1") (pintype "power_in"))
      (node (ref "U5") (pin "A8") (pinfunction "VDDQ2_A8") (pintype "power_in"))
      (node (ref "U5") (pin "B2") (pinfunction "VDD1_B2") (pintype "power_in"))
      (node (ref "U5") (pin "C1") (pinfunction "VDDQ3_C1") (pintype "power_in"))
      (node (ref "U5") (pin "C9") (pinfunction "VDDQ4_C9") (pintype "power_in"))
      (node (ref "U5") (pin "D2") (pinfunction "VDDQ5_D2") (pintype "power_in"))
      (node (ref "U5") (pin "D9") (pinfunction "VDD2_D9") (pintype "power_in"))
      (node (ref "U5") (pin "E9") (pinfunction "VDDQ6_E9") (pintype "power_in"))
      (node (ref "U5") (pin "F1") (pinfunction "VDDQ7_F1") (pintype "power_in"))
      (node (ref "U5") (pin "G7") (pinfunction "VDD3_G7") (pintype "power_in"))
      (node (ref "U5") (pin "H2") (pinfunction "VDDQ8_H2") (pintype "power_in"))
      (node (ref "U5") (pin "H9") (pinfunction "VDDQ9_H9") (pintype "power_in"))
      (node (ref "U5") (pin "K2") (pinfunction "VDD4_K2") (pintype "power_in"))
      (node (ref "U5") (pin "K8") (pinfunction "VDD5_K8") (pintype "power_in"))
      (node (ref "U5") (pin "N1") (pinfunction "VDD6_N1") (pintype "power_in"))
      (node (ref "U5") (pin "N9") (pinfunction "VDD7_N9") (pintype "power_in"))
      (node (ref "U5") (pin "R1") (pinfunction "VDD8_R1") (pintype "power_in"))
      (node (ref "U5") (pin "R9") (pinfunction "VDD9_R9") (pintype "power_in"))
    )
    (net (code "3") (name "+DDR_VREF") (class "Default")
      (node (ref "C10") (pin "1") (pinfunction "1_1") (pintype "passive"))
      (node (ref "C11") (pin "1") (pinfunction "1_1") (pintype "passive"))
      (node (ref "C3") (pin "1") (pinfunction "1_1") (pintype "passive"))
      (node (ref "C392") (pin "2") (pinfunction "2_2") (pintype "passive"))
      (node (ref "C393") (pin "1") (pinfunction "1_1") (pintype "passive"))
      (node (ref "C4") (pin "1") (pinfunction "1_1") (pintype "passive"))
      (node (ref "C5") (pin "1") (pinfunction "1_1") (pintype "passive"))
      (node (ref "C6") (pin "1") (pinfunction "1_1") (pintype "passive"))
      (node (ref "C7") (pin "1") (pinfunction "1_1") (pintype "passive"))
      (node (ref "C8") (pin "1") (pinfunction "1_1") (pintype "passive"))
      (node (ref "C9") (pin "1") (pinfunction "1_1") (pintype "passive"))
      (node (ref "R245") (pin "1") (pinfunction "1_1") (pintype "passive"))
      (node (ref "R274") (pin "2") (pinfunction "2_2") (pintype "passive"))
      (node (ref "U1") (pin "AC2") (pinfunction "DRAM_VREF_AC2") (pintype "power_in"))
      (node (ref "U2") (pin "H1") (pinfunction "VREFDQ_H1") (pintype "input"))
      (node (ref "U2") (pin "M8") (pinfunction "VREFCA_M8") (pintype "input"))
      (node (ref "U3") (pin "H1") (pinfunction "VREFDQ_H1") (pintype "input"))
      (node (ref "U3") (pin "M8") (pinfunction "VREFCA_M8") (pintype "input"))
      (node (ref "U4") (pin "H1") (pinfunction "VREFDQ_H1") (pintype "input"))
      (node (ref "U4") (pin "M8") (pinfunction "VREFCA_M8") (pintype "input"))
      (node (ref "U5") (pin "H1") (pinfunction "VREFDQ_H1") (pintype "input"))
      (node (ref "U5") (pin "M8") (pinfunction "VREFCA_M8") (pintype "input"))
    )
    (net (code "4") (name "/DRAM0_ZQ") (class "Default")
      (node (ref "R4") (pin "2") (pinfunction "2_2") (pintype "passive"))
      (node (ref "U2") (pin "L8") (pinfunction "ZQ_L8") (pintype "passive"))
    )
    (net (code "5") (name "/DRAM0_ZQ1") (class "Default")
      (node (ref "R306") (pin "2") (pinfunction "2_2") (pintype "passive"))
      (node (ref "U2") (pin "L9") (pinfunction "NC_L9_L9") (pintype "passive"))
    )
    (net (code "6") (name "/DRAM1_ZQ") (class "Default")
      (node (ref "R5") (pin "2") (pinfunction "2_2") (pintype "passive"))
      (node (ref "U3") (pin "L8") (pinfunction "ZQ_L8") (pintype "passive"))
    )
    (net (code "7") (name "/DRAM1_ZQ1") (class "Default")
      (node (ref "R307") (pin "2") (pinfunction "2_2") (pintype "passive"))
      (node (ref "U3") (pin "L9") (pinfunction "NC_L9_L9") (pintype "passive"))
    )
    (net (code "8") (name "/DRAM2_ZQ") (class "Default")
      (node (ref "R8") (pin "2") (pinfunction "2_2") (pintype "passive"))
      (node (ref "U4") (pin "L8") (pinfunction "ZQ_L8") (pintype "passive"))
    )
    (net (code "9") (name "/DRAM2_ZQ1") (class "Default")
      (node (ref "R308") (pin "2") (pinfunction "2_2") (pintype "passive"))
      (node (ref "U4") (pin "L9") (pinfunction "NC_L9_L9") (pintype "passive"))
    )
    (net (code "10") (name "/DRAM3_ZQ") (class "Default")
      (node (ref "R9") (pin "2") (pinfunction "2_2") (pintype "passive"))
      (node (ref "U5") (pin "L8") (pinfunction "ZQ_L8") (pintype "passive"))
    )
    (net (code "11") (name "/DRAM3_ZQ1") (class "Default")
      (node (ref "R309") (pin "2") (pinfunction "2_2") (pintype "passive"))
      (node (ref "U5") (pin "L9") (pinfunction "NC_L9_L9") (pintype "passive"))
    )
    (net (code "12") (name "/DRAM_A0") (class "Default")
      (node (ref "R1") (pin "1") (pinfunction "1_1") (pintype "passive"))
      (node (ref "U1") (pin "AC14") (pinfunction "DRAM_A0_AC14") (pintype "output"))
      (node (ref "U2") (pin "N3") (pinfunction "A0_N3") (pintype "input"))
      (node (ref "U3") (pin "N3") (pinfunction "A0_N3") (pintype "input"))
      (node (ref "U4") (pin "N3") (pinfunction "A0_N3") (pintype "input"))
      (node (ref "U5") (pin "N3") (pinfunction "A0_N3") (pintype "input"))
    )
    (net (code "13") (name "/DRAM_A1") (class "Default")
      (node (ref "R3") (pin "1") (pinfunction "1_1") (pintype "passive"))
      (node (ref "U1") (pin "AB14") (pinfunction "DRAM_A1_AB14") (pintype "output"))
      (node (ref "U2") (pin "P7") (pinfunction "A1_P7") (pintype "input"))
      (node (ref "U3") (pin "P7") (pinfunction "A1_P7") (pintype "input"))
      (node (ref "U4") (pin "P7") (pinfunction "A1_P7") (pintype "input"))
      (node (ref "U5") (pin "P7") (pinfunction "A1_P7") (pintype "input"))
    )
    (net (code "14") (name "/DRAM_A2") (class "Default")
      (node (ref "R12") (pin "1") (pinfunction "1_1") (pintype "passive"))
      (node (ref "U1") (pin "AA14") (pinfunction "DRAM_A2_AA14") (pintype "output"))
      (node (ref "U2") (pin "P3") (pinfunction "A2_P3") (pintype "input"))
      (node (ref "U3") (pin "P3") (pinfunction "A2_P3") (pintype "input"))
      (node (ref "U4") (pin "P3") (pinfunction "A2_P3") (pintype "input"))
      (node (ref "U5") (pin "P3") (pinfunction "A2_P3") (pintype "input"))
    )
    (net (code "15") (name "/DRAM_A3") (class "Default")
      (node (ref "R31") (pin "1") (pinfunction "1_1") (pintype "passive"))
      (node (ref "U1") (pin "Y14") (pinfunction "DRAM_A3_Y14") (pintype "output"))
      (node (ref "U2") (pin "N2") (pinfunction "A3_N2") (pintype "input"))
      (node (ref "U3") (pin "N2") (pinfunction "A3_N2") (pintype "input"))
      (node (ref "U4") (pin "N2") (pinfunction "A3_N2") (pintype "input"))
      (node (ref "U5") (pin "N2") (pinfunction "A3_N2") (pintype "input"))
    )
    (net (code "16") (name "/DRAM_A4") (class "Default")
      (node (ref "R38") (pin "1") (pinfunction "1_1") (pintype "passive"))
      (node (ref "U1") (pin "W14") (pinfunction "DRAM_A4_W14") (pintype "output"))
      (node (ref "U2") (pin "P8") (pinfunction "A4_P8") (pintype "input"))
      (node (ref "U3") (pin "P8") (pinfunction "A4_P8") (pintype "input"))
      (node (ref "U4") (pin "P8") (pinfunction "A4_P8") (pintype "input"))
      (node (ref "U5") (pin "P8") (pinfunction "A4_P8") (pintype "input"))
    )
    (net (code "17") (name "/DRAM_A5") (class "Default")
      (node (ref "R40") (pin "1") (pinfunction "1_1") (pintype "passive"))
      (node (ref "U1") (pin "AE13") (pinfunction "DRAM_A5_AE13") (pintype "output"))
      (node (ref "U2") (pin "P2") (pinfunction "A5_P2") (pintype "input"))
      (node (ref "U3") (pin "P2") (pinfunction "A5_P2") (pintype "input"))
      (node (ref "U4") (pin "P2") (pinfunction "A5_P2") (pintype "input"))
      (node (ref "U5") (pin "P2") (pinfunction "A5_P2") (pintype "input"))
    )
    (net (code "18") (name "/DRAM_A6") (class "Default")
      (node (ref "R44") (pin "1") (pinfunction "1_1") (pintype "passive"))
      (node (ref "U1") (pin "AC13") (pinfunction "DRAM_A6_AC13") (pintype "output"))
      (node (ref "U2") (pin "R8") (pinfunction "A6_R8") (pintype "input"))
      (node (ref "U3") (pin "R8") (pinfunction "A6_R8") (pintype "input"))
      (node (ref "U4") (pin "R8") (pinfunction "A6_R8") (pintype "input"))
      (node (ref "U5") (pin "R8") (pinfunction "A6_R8") (pintype "input"))
    )
    (net (code "19") (name "/DRAM_A7") (class "Default")
      (node (ref "R50") (pin "1") (pinfunction "1_1") (pintype "passive"))
      (node (ref "U1") (pin "Y13") (pinfunction "DRAM_A7_Y13") (pintype "output"))
      (node (ref "U2") (pin "R2") (pinfunction "A7_R2") (pintype "input"))
      (node (ref "U3") (pin "R2") (pinfunction "A7_R2") (pintype "input"))
      (node (ref "U4") (pin "R2") (pinfunction "A7_R2") (pintype "input"))
      (node (ref "U5") (pin "R2") (pinfunction "A7_R2") (pintype "input"))
    )
    (net (code "20") (name "/DRAM_A8") (class "Default")
      (node (ref "R72") (pin "1") (pinfunction "1_1") (pintype "passive"))
      (node (ref "U1") (pin "AB13") (pinfunction "DRAM_A8_AB13") (pintype "output"))
      (node (ref "U2") (pin "T8") (pinfunction "A8_T8") (pintype "input"))
      (node (ref "U3") (pin "T8") (pinfunction "A8_T8") (pintype "input"))
      (node (ref "U4") (pin "T8") (pinfunction "A8_T8") (pintype "input"))
      (node (ref "U5") (pin "T8") (pinfunction "A8_T8") (pintype "input"))
    )
    (net (code "21") (name "/DRAM_A9") (class "Default")
      (node (ref "R79") (pin "1") (pinfunction "1_1") (pintype "passive"))
      (node (ref "U1") (pin "AE12") (pinfunction "DRAM_A9_AE12") (pintype "output"))
      (node (ref "U2") (pin "R3") (pinfunction "A9_R3") (pintype "input"))
      (node (ref "U3") (pin "R3") (pinfunction "A9_R3") (pintype "input"))
      (node (ref "U4") (pin "R3") (pinfunction "A9_R3") (pintype "input"))
      (node (ref "U5") (pin "R3") (pinfunction "A9_R3") (pintype "input"))
    )
    (net (code "22") (name "/DRAM_A10") (class "Default")
      (node (ref "R103") (pin "1") (pinfunction "1_1") (pintype "passive"))
      (node (ref "U1") (pin "AA15") (pinfunction "DRAM_A10_AA15") (pintype "output"))
      (node (ref "U2") (pin "L7") (pinfunction "A10/AP_L7") (pintype "input"))
      (node (ref "U3") (pin "L7") (pinfunction "A10/AP_L7") (pintype "input"))
      (node (ref "U4") (pin "L7") (pinfunction "A10/AP_L7") (pintype "input"))
      (node (ref "U5") (pin "L7") (pinfunction "A10/AP_L7") (pintype "input"))
    )
    (net (code "23") (name "/DRAM_A11") (class "Default")
      (node (ref "R105") (pin "1") (pinfunction "1_1") (pintype "passive"))
      (node (ref "U1") (pin "AC12") (pinfunction "DRAM_A11_AC12") (pintype "output"))
      (node (ref "U2") (pin "R7") (pinfunction "A11_R7") (pintype "input"))
      (node (ref "U3") (pin "R7") (pinfunction "A11_R7") (pintype "input"))
      (node (ref "U4") (pin "R7") (pinfunction "A11_R7") (pintype "input"))
      (node (ref "U5") (pin "R7") (pinfunction "A11_R7") (pintype "input"))
    )
    (net (code "24") (name "/DRAM_A12") (class "Default")
      (node (ref "R106") (pin "1") (pinfunction "1_1") (pintype "passive"))
      (node (ref "U1") (pin "AD12") (pinfunction "DRAM_A12_AD12") (pintype "output"))
      (node (ref "U2") (pin "N7") (pinfunction "A12/~{BC}_N7") (pintype "input"))
      (node (ref "U3") (pin "N7") (pinfunction "A12/~{BC}_N7") (pintype "input"))
      (node (ref "U4") (pin "N7") (pinfunction "A12/~{BC}_N7") (pintype "input"))
      (node (ref "U5") (pin "N7") (pinfunction "A12/~{BC}_N7") (pintype "input"))
    )
    (net (code "25") (name "/DRAM_A13") (class "Default")
      (node (ref "R107") (pin "1") (pinfunction "1_1") (pintype "passive"))
      (node (ref "U1") (pin "AC17") (pinfunction "DRAM_A13_AC17") (pintype "output"))
      (node (ref "U2") (pin "T3") (pinfunction "A13_T3") (pintype "input"))
      (node (ref "U3") (pin "T3") (pinfunction "A13_T3") (pintype "input"))
      (node (ref "U4") (pin "T3") (pinfunction "A13_T3") (pintype "input"))
      (node (ref "U5") (pin "T3") (pinfunction "A13_T3") (pintype "input"))
    )
    (net (code "26") (name "/DRAM_A14") (class "Default")
      (node (ref "R108") (pin "1") (pinfunction "1_1") (pintype "passive"))
      (node (ref "U1") (pin "AA12") (pinfunction "DRAM_A14_AA12") (pintype "output"))
      (node (ref "U2") (pin "T7") (pinfunction "A14_T7") (pintype "passive"))
      (node (ref "U3") (pin "T7") (pinfunction "A14_T7") (pintype "passive"))
      (node (ref "U4") (pin "T7") (pinfunction "A14_T7") (pintype "passive"))
      (node (ref "U5") (pin "T7") (pinfunction "A14_T7") (pintype "passive"))
    )
    (net (code "27") (name "/DRAM_A15") (class "Default")
      (node (ref "R111") (pin "1") (pinfunction "1_1") (pintype "passive"))
      (node (ref "U1") (pin "Y12") (pinfunction "DRAM_A15_Y12") (pintype "output"))
      (node (ref "U2") (pin "M7") (pinfunction "NC_M7_M7") (pintype "passive"))
      (node (ref "U3") (pin "M7") (pinfunction "NC_M7_M7") (pintype "passive"))
      (node (ref "U4") (pin "M7") (pinfunction "NC_M7_M7") (pintype "passive"))
      (node (ref "U5") (pin "M7") (pinfunction "NC_M7_M7") (pintype "passive"))
    )
    (net (code "29") (name "/DRAM_CAS_B") (class "Default")
      (node (ref "R39") (pin "1") (pinfunction "1_1") (pintype "passive"))
      (node (ref "U1") (pin "AE16") (pinfunction "DRAM_CAS_AE16") (pintype "output"))
      (node (ref "U2") (pin "K3") (pinfunction "~{CAS}_K3") (pintype "input"))
      (node (ref "U3") (pin "K3") (pinfunction "~{CAS}_K3") (pintype "input"))
      (node (ref "U4") (pin "K3") (pinfunction "~{CAS}_K3") (pintype "input"))
      (node (ref "U5") (pin "K3") (pinfunction "~{CAS}_K3") (pintype "input"))
    )
    (net (code "30") (name "/DRAM_CLK0_N") (class "Default")
      (node (ref "C327") (pin "2") (pinfunction "2_2") (pintype "passive"))
      (node (ref "R112") (pin "2") (pinfunction "2_2") (pintype "passive"))
      (node (ref "U1") (pin "AE15") (pinfunction "~{DRAM_SDCLK_0}_AE15") (pintype "output"))
      (node (ref "U2") (pin "K7") (pinfunction "~{CK}_K7") (pintype "input"))
      (node (ref "U3") (pin "K7") (pinfunction "~{CK}_K7") (pintype "input"))
      (node (ref "U4") (pin "K7") (pinfunction "~{CK}_K7") (pintype "input"))
      (node (ref "U5") (pin "K7") (pinfunction "~{CK}_K7") (pintype "input"))
    )
    (net (code "31") (name "/DRAM_CLK0_P") (class "Default")
      (node (ref "C327") (pin "1") (pinfunction "1_1") (pintype "passive"))
      (node (ref "R253") (pin "2") (pinfunction "2_2") (pintype "passive"))
      (node (ref "U1") (pin "AD15") (pinfunction "DRAM_SDCLK_0_AD15") (pintype "output"))
      (node (ref "U2") (pin "J7") (pinfunction "CK_J7") (pintype "input"))
      (node (ref "U3") (pin "J7") (pinfunction "CK_J7") (pintype "input"))
      (node (ref "U4") (pin "J7") (pinfunction "CK_J7") (pintype "input"))
      (node (ref "U5") (pin "J7") (pinfunction "CK_J7") (pintype "input"))
    )
    (net (code "32") (name "/DRAM_CLK0_T_CAP") (class "Default")
      (node (ref "C322") (pin "1") (pinfunction "1_1") (pintype "passive"))
      (node (ref "R112") (pin "1") (pinfunction "1_1") (pintype "passive"))
      (node (ref "R253") (pin "1") (pinfunction "1_1") (pintype "passive"))
    )
    (net (code "33") (name "/DRAM_CLK1_N") (class "Default")
      (node (ref "C328") (pin "2") (pinfunction "2_2") (pintype "passive"))
      (node (ref "R113") (pin "2") (pinfunction "2_2") (pintype "passive"))
      (node (ref "U1") (pin "AE14") (pinfunction "~{DRAM_SDCLK_1}_AE14") (pintype "output"))
    )
    (net (code "34") (name "/DRAM_CLK1_P") (class "Default")
      (node (ref "C328") (pin "1") (pinfunction "1_1") (pintype "passive"))
      (node (ref "R256") (pin "2") (pinfunction "2_2") (pintype "passive"))
      (node (ref "U1") (pin "AD14") (pinfunction "DRAM_SDCLK_1_AD14") (pintype "output"))
    )
    (net (code "35") (name "/DRAM_CLK1_T_CAP") (class "Default")
      (node (ref "C323") (pin "1") (pinfunction "1_1") (pintype "passive"))
      (node (ref "R113") (pin "1") (pinfunction "1_1") (pintype "passive"))
      (node (ref "R256") (pin "1") (pinfunction "1_1") (pintype "passive"))
    )
    (net (code "36") (name "/DRAM_CS0_B") (class "Default")
      (node (ref "R66") (pin "1") (pinfunction "1_1") (pintype "passive"))
      (node (ref "U1") (pin "Y16") (pinfunction "DRAM_CS0_Y16") (pintype "output"))
      (node (ref "U2") (pin "L2") (pinfunction "~{CS}_L2") (pintype "input"))
      (node (ref "U3") (pin "L2") (pinfunction "~{CS}_L2") (pintype "input"))
      (node (ref "U4") (pin "L2") (pinfunction "~{CS}_L2") (pintype "input"))
      (node (ref "U5") (pin "L2") (pinfunction "~{CS}_L2") (pintype "input"))
    )
    (net (code "37") (name "/DRAM_D0") (class "Default")
      (node (ref "U1") (pin "AD2") (pinfunction "DRAM_D0_AD2") (pintype "bidirectional"))
      (node (ref "U2") (pin "E3") (pinfunction "DQ0_E3") (pintype "bidirectional"))
    )
    (net (code "38") (name "/DRAM_D1") (class "Default")
      (node (ref "U1") (pin "AE2") (pinfunction "DRAM_D1_AE2") (pintype "bidirectional"))
      (node (ref "U2") (pin "H3") (pinfunction "DQ4_H3") (pintype "bidirectional"))
    )
    (net (code "39") (name "/DRAM_D2") (class "Default")
      (node (ref "U1") (pin "AC4") (pinfunction "DRAM_D2_AC4") (pintype "bidirectional"))
      (node (ref "U2") (pin "H7") (pinfunction "DQ7_H7") (pintype "bidirectional"))
    )
    (net (code "40") (name "/DRAM_D3") (class "Default")
      (node (ref "U1") (pin "AA5") (pinfunction "DRAM_D3_AA5") (pintype "bidirectional"))
      (node (ref "U2") (pin "F8") (pinfunction "DQ3_F8") (pintype "bidirectional"))
    )
    (net (code "41") (name "/DRAM_D4") (class "Default")
      (node (ref "U1") (pin "AC1") (pinfunction "DRAM_D4_AC1") (pintype "bidirectional"))
      (node (ref "U2") (pin "F2") (pinfunction "DQ2_F2") (pintype "bidirectional"))
    )
    (net (code "42") (name "/DRAM_D5") (class "Default")
      (node (ref "U1") (pin "AD1") (pinfunction "DRAM_D5_AD1") (pintype "bidirectional"))
      (node (ref "U2") (pin "G2") (pinfunction "DQ6_G2") (pintype "bidirectional"))
    )
    (net (code "43") (name "/DRAM_D6") (class "Default")
      (node (ref "U1") (pin "AB4") (pinfunction "DRAM_D6_AB4") (pintype "bidirectional"))
      (node (ref "U2") (pin "F7") (pinfunction "DQ1_F7") (pintype "bidirectional"))
    )
    (net (code "44") (name "/DRAM_D7") (class "Default")
      (node (ref "U1") (pin "AE4") (pinfunction "DRAM_D7_AE4") (pintype "bidirectional"))
      (node (ref "U2") (pin "H8") (pinfunction "DQ5_H8") (pintype "bidirectional"))
    )
    (net (code "45") (name "/DRAM_D8") (class "Default")
      (node (ref "U1") (pin "AD5") (pinfunction "DRAM_D8_AD5") (pintype "bidirectional"))
      (node (ref "U2") (pin "D7") (pinfunction "DQ8_D7") (pintype "bidirectional"))
    )
    (net (code "46") (name "/DRAM_D9") (class "Default")
      (node (ref "U1") (pin "AE5") (pinfunction "DRAM_D9_AE5") (pintype "bidirectional"))
      (node (ref "U2") (pin "C3") (pinfunction "DQ9_C3") (pintype "bidirectional"))
    )
    (net (code "47") (name "/DRAM_D10") (class "Default")
      (node (ref "U1") (pin "AA6") (pinfunction "DRAM_D10_AA6") (pintype "bidirectional"))
      (node (ref "U2") (pin "B8") (pinfunction "DQ14_B8") (pintype "bidirectional"))
    )
    (net (code "48") (name "/DRAM_D11") (class "Default")
      (node (ref "U1") (pin "AE7") (pinfunction "DRAM_D11_AE7") (pintype "bidirectional"))
      (node (ref "U2") (pin "C8") (pinfunction "DQ10_C8") (pintype "bidirectional"))
    )
    (net (code "49") (name "/DRAM_D12") (class "Default")
      (node (ref "U1") (pin "AB5") (pinfunction "DRAM_D12_AB5") (pintype "bidirectional"))
      (node (ref "U2") (pin "C2") (pinfunction "DQ11_C2") (pintype "bidirectional"))
    )
    (net (code "50") (name "/DRAM_D13") (class "Default")
      (node (ref "U1") (pin "AC5") (pinfunction "DRAM_D13_AC5") (pintype "bidirectional"))
      (node (ref "U2") (pin "A3") (pinfunction "DQ15_A3") (pintype "bidirectional"))
    )
    (net (code "51") (name "/DRAM_D14") (class "Default")
      (node (ref "U1") (pin "AB6") (pinfunction "DRAM_D14_AB6") (pintype "bidirectional"))
      (node (ref "U2") (pin "A2") (pinfunction "DQ13_A2") (pintype "bidirectional"))
    )
    (net (code "52") (name "/DRAM_D15") (class "Default")
      (node (ref "U1") (pin "AC7") (pinfunction "DRAM_D15_AC7") (pintype "bidirectional"))
      (node (ref "U2") (pin "A7") (pinfunction "DQ12_A7") (pintype "bidirectional"))
    )
    (net (code "53") (name "/DRAM_D16") (class "Default")
      (node (ref "U1") (pin "AB7") (pinfunction "DRAM_D16_AB7") (pintype "bidirectional"))
      (node (ref "U3") (pin "E3") (pinfunction "DQ0_E3") (pintype "bidirectional"))
    )
    (net (code "54") (name "/DRAM_D17") (class "Default")
      (node (ref "U1") (pin "AA8") (pinfunction "DRAM_D17_AA8") (pintype "bidirectional"))
      (node (ref "U3") (pin "F7") (pinfunction "DQ1_F7") (pintype "bidirectional"))
    )
    (net (code "55") (name "/DRAM_D18") (class "Default")
      (node (ref "U1") (pin "AB9") (pinfunction "DRAM_D18_AB9") (pintype "bidirectional"))
      (node (ref "U3") (pin "H3") (pinfunction "DQ4_H3") (pintype "bidirectional"))
    )
    (net (code "56") (name "/DRAM_D19") (class "Default")
      (node (ref "U1") (pin "Y9") (pinfunction "DRAM_D19_Y9") (pintype "bidirectional"))
      (node (ref "U3") (pin "H8") (pinfunction "DQ5_H8") (pintype "bidirectional"))
    )
    (net (code "57") (name "/DRAM_D20") (class "Default")
      (node (ref "U1") (pin "Y7") (pinfunction "DRAM_D20_Y7") (pintype "bidirectional"))
      (node (ref "U3") (pin "G2") (pinfunction "DQ6_G2") (pintype "bidirectional"))
    )
    (net (code "58") (name "/DRAM_D21") (class "Default")
      (node (ref "U1") (pin "Y8") (pinfunction "DRAM_D21_Y8") (pintype "bidirectional"))
      (node (ref "U3") (pin "F8") (pinfunction "DQ3_F8") (pintype "bidirectional"))
    )
    (net (code "59") (name "/DRAM_D22") (class "Default")
      (node (ref "U1") (pin "AC8") (pinfunction "DRAM_D22_AC8") (pintype "bidirectional"))
      (node (ref "U3") (pin "F2") (pinfunction "DQ2_F2") (pintype "bidirectional"))
    )
    (net (code "60") (name "/DRAM_D23") (class "Default")
      (node (ref "U1") (pin "AA9") (pinfunction "DRAM_D23_AA9") (pintype "bidirectional"))
      (node (ref "U3") (pin "H7") (pinfunction "DQ7_H7") (pintype "bidirectional"))
    )
    (net (code "61") (name "/DRAM_D24") (class "Default")
      (node (ref "U1") (pin "AE9") (pinfunction "DRAM_D24_AE9") (pintype "bidirectional"))
      (node (ref "U3") (pin "D7") (pinfunction "DQ8_D7") (pintype "bidirectional"))
    )
    (net (code "62") (name "/DRAM_D25") (class "Default")
      (node (ref "U1") (pin "Y10") (pinfunction "DRAM_D25_Y10") (pintype "bidirectional"))
      (node (ref "U3") (pin "A2") (pinfunction "DQ13_A2") (pintype "bidirectional"))
    )
    (net (code "63") (name "/DRAM_D26") (class "Default")
      (node (ref "U1") (pin "AE11") (pinfunction "DRAM_D26_AE11") (pintype "bidirectional"))
      (node (ref "U3") (pin "B8") (pinfunction "DQ14_B8") (pintype "bidirectional"))
    )
    (net (code "64") (name "/DRAM_D27") (class "Default")
      (node (ref "U1") (pin "AB11") (pinfunction "DRAM_D27_AB11") (pintype "bidirectional"))
      (node (ref "U3") (pin "C2") (pinfunction "DQ11_C2") (pintype "bidirectional"))
    )
    (net (code "65") (name "/DRAM_D28") (class "Default")
      (node (ref "U1") (pin "AC9") (pinfunction "DRAM_D28_AC9") (pintype "bidirectional"))
      (node (ref "U3") (pin "C3") (pinfunction "DQ9_C3") (pintype "bidirectional"))
    )
    (net (code "66") (name "/DRAM_D29") (class "Default")
      (node (ref "U1") (pin "AD9") (pinfunction "DRAM_D29_AD9") (pintype "bidirectional"))
      (node (ref "U3") (pin "A7") (pinfunction "DQ12_A7") (pintype "bidirectional"))
    )
    (net (code "67") (name "/DRAM_D30") (class "Default")
      (node (ref "U1") (pin "AD11") (pinfunction "DRAM_D30_AD11") (pintype "bidirectional"))
      (node (ref "U3") (pin "C8") (pinfunction "DQ10_C8") (pintype "bidirectional"))
    )
    (net (code "68") (name "/DRAM_D31") (class "Default")
      (node (ref "U1") (pin "AC11") (pinfunction "DRAM_D31_AC11") (pintype "bidirectional"))
      (node (ref "U3") (pin "A3") (pinfunction "DQ15_A3") (pintype "bidirectional"))
    )
    (net (code "69") (name "/DRAM_D32") (class "Default")
      (node (ref "U1") (pin "AA17") (pinfunction "DRAM_D32_AA17") (pintype "bidirectional"))
      (node (ref "U4") (pin "E3") (pinfunction "DQ0_E3") (pintype "bidirectional"))
    )
    (net (code "70") (name "/DRAM_D33") (class "Default")
      (node (ref "U1") (pin "AA18") (pinfunction "DRAM_D33_AA18") (pintype "bidirectional"))
      (node (ref "U4") (pin "H3") (pinfunction "DQ4_H3") (pintype "bidirectional"))
    )
    (net (code "71") (name "/DRAM_D34") (class "Default")
      (node (ref "U1") (pin "AC18") (pinfunction "DRAM_D34_AC18") (pintype "bidirectional"))
      (node (ref "U4") (pin "F7") (pinfunction "DQ1_F7") (pintype "bidirectional"))
    )
    (net (code "72") (name "/DRAM_D35") (class "Default")
      (node (ref "U1") (pin "AE19") (pinfunction "DRAM_D35_AE19") (pintype "bidirectional"))
      (node (ref "U4") (pin "H7") (pinfunction "DQ7_H7") (pintype "bidirectional"))
    )
    (net (code "73") (name "/DRAM_D36") (class "Default")
      (node (ref "U1") (pin "Y17") (pinfunction "DRAM_D36_Y17") (pintype "bidirectional"))
      (node (ref "U4") (pin "G2") (pinfunction "DQ6_G2") (pintype "bidirectional"))
    )
    (net (code "74") (name "/DRAM_D37") (class "Default")
      (node (ref "U1") (pin "Y18") (pinfunction "DRAM_D37_Y18") (pintype "bidirectional"))
      (node (ref "U4") (pin "F2") (pinfunction "DQ2_F2") (pintype "bidirectional"))
    )
    (net (code "75") (name "/DRAM_D38") (class "Default")
      (node (ref "U1") (pin "AB19") (pinfunction "DRAM_D38_AB19") (pintype "bidirectional"))
      (node (ref "U4") (pin "F8") (pinfunction "DQ3_F8") (pintype "bidirectional"))
    )
    (net (code "76") (name "/DRAM_D39") (class "Default")
      (node (ref "U1") (pin "AC19") (pinfunction "DRAM_D39_AC19") (pintype "bidirectional"))
      (node (ref "U4") (pin "H8") (pinfunction "DQ5_H8") (pintype "bidirectional"))
    )
    (net (code "77") (name "/DRAM_D40") (class "Default")
      (node (ref "U1") (pin "Y19") (pinfunction "DRAM_D40_Y19") (pintype "bidirectional"))
      (node (ref "U4") (pin "D7") (pinfunction "DQ8_D7") (pintype "bidirectional"))
    )
    (net (code "78") (name "/DRAM_D41") (class "Default")
      (node (ref "U1") (pin "AB20") (pinfunction "DRAM_D41_AB20") (pintype "bidirectional"))
      (node (ref "U4") (pin "C2") (pinfunction "DQ11_C2") (pintype "bidirectional"))
    )
    (net (code "79") (name "/DRAM_D42") (class "Default")
      (node (ref "U1") (pin "AB21") (pinfunction "DRAM_D42_AB21") (pintype "bidirectional"))
      (node (ref "U4") (pin "A7") (pinfunction "DQ12_A7") (pintype "bidirectional"))
    )
    (net (code "80") (name "/DRAM_D43") (class "Default")
      (node (ref "U1") (pin "AD21") (pinfunction "DRAM_D43_AD21") (pintype "bidirectional"))
      (node (ref "U4") (pin "C8") (pinfunction "DQ10_C8") (pintype "bidirectional"))
    )
    (net (code "81") (name "/DRAM_D44") (class "Default")
      (node (ref "U1") (pin "Y20") (pinfunction "DRAM_D44_Y20") (pintype "bidirectional"))
      (node (ref "U4") (pin "A2") (pinfunction "DQ13_A2") (pintype "bidirectional"))
    )
    (net (code "82") (name "/DRAM_D45") (class "Default")
      (node (ref "U1") (pin "AA20") (pinfunction "DRAM_D45_AA20") (pintype "bidirectional"))
      (node (ref "U4") (pin "A3") (pinfunction "DQ15_A3") (pintype "bidirectional"))
    )
    (net (code "83") (name "/DRAM_D46") (class "Default")
      (node (ref "U1") (pin "AE21") (pinfunction "DRAM_D46_AE21") (pintype "bidirectional"))
      (node (ref "U4") (pin "B8") (pinfunction "DQ14_B8") (pintype "bidirectional"))
    )
    (net (code "84") (name "/DRAM_D47") (class "Default")
      (node (ref "U1") (pin "AC21") (pinfunction "DRAM_D47_AC21") (pintype "bidirectional"))
      (node (ref "U4") (pin "C3") (pinfunction "DQ9_C3") (pintype "bidirectional"))
    )
    (net (code "85") (name "/DRAM_D48") (class "Default")
      (node (ref "U1") (pin "AC22") (pinfunction "DRAM_D48_AC22") (pintype "bidirectional"))
      (node (ref "U5") (pin "E3") (pinfunction "DQ0_E3") (pintype "bidirectional"))
    )
    (net (code "86") (name "/DRAM_D49") (class "Default")
      (node (ref "U1") (pin "AE22") (pinfunction "DRAM_D49_AE22") (pintype "bidirectional"))
      (node (ref "U5") (pin "G2") (pinfunction "DQ6_G2") (pintype "bidirectional"))
    )
    (net (code "87") (name "/DRAM_D50") (class "Default")
      (node (ref "U1") (pin "AE24") (pinfunction "DRAM_D50_AE24") (pintype "bidirectional"))
      (node (ref "U5") (pin "H7") (pinfunction "DQ7_H7") (pintype "bidirectional"))
    )
    (net (code "88") (name "/DRAM_D51") (class "Default")
      (node (ref "U1") (pin "AC24") (pinfunction "DRAM_D51_AC24") (pintype "bidirectional"))
      (node (ref "U5") (pin "F8") (pinfunction "DQ3_F8") (pintype "bidirectional"))
    )
    (net (code "89") (name "/DRAM_D52") (class "Default")
      (node (ref "U1") (pin "AB22") (pinfunction "DRAM_D52_AB22") (pintype "bidirectional"))
      (node (ref "U5") (pin "F2") (pinfunction "DQ2_F2") (pintype "bidirectional"))
    )
    (net (code "90") (name "/DRAM_D53") (class "Default")
      (node (ref "U1") (pin "AC23") (pinfunction "DRAM_D53_AC23") (pintype "bidirectional"))
      (node (ref "U5") (pin "H3") (pinfunction "DQ4_H3") (pintype "bidirectional"))
    )
    (net (code "91") (name "/DRAM_D54") (class "Default")
      (node (ref "U1") (pin "AD25") (pinfunction "DRAM_D54_AD25") (pintype "bidirectional"))
      (node (ref "U5") (pin "F7") (pinfunction "DQ1_F7") (pintype "bidirectional"))
    )
    (net (code "92") (name "/DRAM_D55") (class "Default")
      (node (ref "U1") (pin "AC25") (pinfunction "DRAM_D55_AC25") (pintype "bidirectional"))
      (node (ref "U5") (pin "H8") (pinfunction "DQ5_H8") (pintype "bidirectional"))
    )
    (net (code "93") (name "/DRAM_D56") (class "Default")
      (node (ref "U1") (pin "AB25") (pinfunction "DRAM_D56_AB25") (pintype "bidirectional"))
      (node (ref "U5") (pin "D7") (pinfunction "DQ8_D7") (pintype "bidirectional"))
    )
    (net (code "94") (name "/DRAM_D57") (class "Default")
      (node (ref "U1") (pin "AA21") (pinfunction "DRAM_D57_AA21") (pintype "bidirectional"))
      (node (ref "U5") (pin "C2") (pinfunction "DQ11_C2") (pintype "bidirectional"))
    )
    (net (code "95") (name "/DRAM_D58") (class "Default")
      (node (ref "U1") (pin "Y25") (pinfunction "DRAM_D58_Y25") (pintype "bidirectional"))
      (node (ref "U5") (pin "B8") (pinfunction "DQ14_B8") (pintype "bidirectional"))
    )
    (net (code "96") (name "/DRAM_D59") (class "Default")
      (node (ref "U1") (pin "Y22") (pinfunction "DRAM_D59_Y22") (pintype "bidirectional"))
      (node (ref "U5") (pin "A2") (pinfunction "DQ13_A2") (pintype "bidirectional"))
    )
    (net (code "97") (name "/DRAM_D60") (class "Default")
      (node (ref "U1") (pin "AB23") (pinfunction "DRAM_D60_AB23") (pintype "bidirectional"))
      (node (ref "U5") (pin "C3") (pinfunction "DQ9_C3") (pintype "bidirectional"))
    )
    (net (code "98") (name "/DRAM_D61") (class "Default")
      (node (ref "U1") (pin "AA23") (pinfunction "DRAM_D61_AA23") (pintype "bidirectional"))
      (node (ref "U5") (pin "A3") (pinfunction "DQ15_A3") (pintype "bidirectional"))
    )
    (net (code "99") (name "/DRAM_D62") (class "Default")
      (node (ref "U1") (pin "Y23") (pinfunction "DRAM_D62_Y23") (pintype "bidirectional"))
      (node (ref "U5") (pin "A7") (pinfunction "DQ12_A7") (pintype "bidirectional"))
    )
    (net (code "100") (name "/DRAM_D63") (class "Default")
      (node (ref "U1") (pin "W25") (pinfunction "DRAM_D63_W25") (pintype "bidirectional"))
      (node (ref "U5") (pin "C8") (pinfunction "DQ10_C8") (pintype "bidirectional"))
    )
    (net (code "101") (name "/DRAM_DQM0") (class "Default")
      (node (ref "U1") (pin "AC3") (pinfunction "DRAM_DQM0_AC3") (pintype "output"))
      (node (ref "U2") (pin "E7") (pinfunction "LDM_E7") (pintype "input"))
    )
    (net (code "102") (name "/DRAM_DQM1") (class "Default")
      (node (ref "U1") (pin "AC6") (pinfunction "DRAM_DQM1_AC6") (pintype "output"))
      (node (ref "U2") (pin "D3") (pinfunction "UDM_D3") (pintype "input"))
    )
    (net (code "103") (name "/DRAM_DQM2") (class "Default")
      (node (ref "U1") (pin "AB8") (pinfunction "DRAM_DQM2_AB8") (pintype "output"))
      (node (ref "U3") (pin "E7") (pinfunction "LDM_E7") (pintype "input"))
    )
    (net (code "104") (name "/DRAM_DQM3") (class "Default")
      (node (ref "U1") (pin "AE10") (pinfunction "DRAM_DQM3_AE10") (pintype "output"))
      (node (ref "U3") (pin "D3") (pinfunction "UDM_D3") (pintype "input"))
    )
    (net (code "105") (name "/DRAM_DQM4") (class "Default")
      (node (ref "U1") (pin "AB18") (pinfunction "DRAM_DQM4_AB18") (pintype "output"))
      (node (ref "U4") (pin "E7") (pinfunction "LDM_E7") (pintype "input"))
    )
    (net (code "106") (name "/DRAM_DQM5") (class "Default")
      (node (ref "U1") (pin "AC20") (pinfunction "DRAM_DQM5_AC20") (pintype "output"))
      (node (ref "U4") (pin "D3") (pinfunction "UDM_D3") (pintype "input"))
    )
    (net (code "107") (name "/DRAM_DQM6") (class "Default")
      (node (ref "U1") (pin "AD24") (pinfunction "DRAM_DQM6_AD24") (pintype "output"))
      (node (ref "U5") (pin "E7") (pinfunction "LDM_E7") (pintype "input"))
    )
    (net (code "108") (name "/DRAM_DQM7") (class "Default")
      (node (ref "U1") (pin "Y21") (pinfunction "DRAM_DQM7_Y21") (pintype "output"))
      (node (ref "U5") (pin "D3") (pinfunction "UDM_D3") (pintype "input"))
    )
    (net (code "109") (name "/DRAM_DQS0_N") (class "Default")
      (node (ref "U1") (pin "AD3") (pinfunction "~{DRAM_SDQS0}_AD3") (pintype "bidirectional"))
      (node (ref "U2") (pin "G3") (pinfunction "~{LDQS}_G3") (pintype "bidirectional"))
    )
    (net (code "110") (name "/DRAM_DQS0_P") (class "Default")
      (node (ref "U1") (pin "AE3") (pinfunction "DRAM_SDQS0_AE3") (pintype "bidirectional"))
      (node (ref "U2") (pin "F3") (pinfunction "LDQS_F3") (pintype "bidirectional"))
    )
    (net (code "111") (name "/DRAM_DQS1_N") (class "Default")
      (node (ref "U1") (pin "AE6") (pinfunction "~{DRAM_SDQS1}_AE6") (pintype "bidirectional"))
      (node (ref "U2") (pin "B7") (pinfunction "~{UDQS}_B7") (pintype "bidirectional"))
    )
    (net (code "112") (name "/DRAM_DQS1_P") (class "Default")
      (node (ref "U1") (pin "AD6") (pinfunction "DRAM_SDQS1_AD6") (pintype "bidirectional"))
      (node (ref "U2") (pin "C7") (pinfunction "UDQS_C7") (pintype "bidirectional"))
    )
    (net (code "113") (name "/DRAM_DQS2_N") (class "Default")
      (node (ref "U1") (pin "AE8") (pinfunction "~{DRAM_SDQS2}_AE8") (pintype "bidirectional"))
      (node (ref "U3") (pin "G3") (pinfunction "~{LDQS}_G3") (pintype "bidirectional"))
    )
    (net (code "114") (name "/DRAM_DQS2_P") (class "Default")
      (node (ref "U1") (pin "AD8") (pinfunction "DRAM_SDQS2_AD8") (pintype "bidirectional"))
      (node (ref "U3") (pin "F3") (pinfunction "LDQS_F3") (pintype "bidirectional"))
    )
    (net (code "115") (name "/DRAM_DQS3_N") (class "Default")
      (node (ref "U1") (pin "AB10") (pinfunction "~{DRAM_SDQS3}_AB10") (pintype "bidirectional"))
      (node (ref "U3") (pin "B7") (pinfunction "~{UDQS}_B7") (pintype "bidirectional"))
    )
    (net (code "116") (name "/DRAM_DQS3_P") (class "Default")
      (node (ref "U1") (pin "AC10") (pinfunction "DRAM_SDQS3_AC10") (pintype "bidirectional"))
      (node (ref "U3") (pin "C7") (pinfunction "UDQS_C7") (pintype "bidirectional"))
    )
    (net (code "117") (name "/DRAM_DQS4_N") (class "Default")
      (node (ref "U1") (pin "AE18") (pinfunction "~{DRAM_SDQS4}_AE18") (pintype "bidirectional"))
      (node (ref "U4") (pin "G3") (pinfunction "~{LDQS}_G3") (pintype "bidirectional"))
    )
    (net (code "118") (name "/DRAM_DQS4_P") (class "Default")
      (node (ref "U1") (pin "AD18") (pinfunction "DRAM_SDQS4_AD18") (pintype "bidirectional"))
      (node (ref "U4") (pin "F3") (pinfunction "LDQS_F3") (pintype "bidirectional"))
    )
    (net (code "119") (name "/DRAM_DQS5_N") (class "Default")
      (node (ref "U1") (pin "AE20") (pinfunction "~{DRAM_SDQS5}_AE20") (pintype "bidirectional"))
      (node (ref "U4") (pin "B7") (pinfunction "~{UDQS}_B7") (pintype "bidirectional"))
    )
    (net (code "120") (name "/DRAM_DQS5_P") (class "Default")
      (node (ref "U1") (pin "AD20") (pinfunction "DRAM_SDQS5_AD20") (pintype "bidirectional"))
      (node (ref "U4") (pin "C7") (pinfunction "UDQS_C7") (pintype "bidirectional"))
    )
    (net (code "121") (name "/DRAM_DQS6_N") (class "Default")
      (node (ref "U1") (pin "AE23") (pinfunction "~{DRAM_SDQS6}_AE23") (pintype "bidirectional"))
      (node (ref "U5") (pin "G3") (pinfunction "~{LDQS}_G3") (pintype "bidirectional"))
    )
    (net (code "122") (name "/DRAM_DQS6_P") (class "Default")
      (node (ref "U1") (pin "AD23") (pinfunction "DRAM_SDQS6_AD23") (pintype "bidirectional"))
      (node (ref "U5") (pin "F3") (pinfunction "LDQS_F3") (pintype "bidirectional"))
    )
    (net (code "123") (name "/DRAM_DQS7_N") (class "Default")
      (node (ref "U1") (pin "AA24") (pinfunction "~{DRAM_SDQS7}_AA24") (pintype "bidirectional"))
      (node (ref "U5") (pin "B7") (pinfunction "~{UDQS}_B7") (pintype "bidirectional"))
    )
    (net (code "124") (name "/DRAM_DQS7_P") (class "Default")
      (node (ref "U1") (pin "AA25") (pinfunction "DRAM_SDQS7_AA25") (pintype "bidirectional"))
      (node (ref "U5") (pin "C7") (pinfunction "UDQS_C7") (pintype "bidirectional"))
    )
    (net (code "126") (name "/DRAM_RAS_B") (class "Default")
      (node (ref "R34") (pin "1") (pinfunction "1_1") (pintype "passive"))
      (node (ref "U1") (pin "AB15") (pinfunction "DRAM_RAS_AB15") (pintype "output"))
      (node (ref "U2") (pin "J3") (pinfunction "~{RAS}_J3") (pintype "input"))
      (node (ref "U3") (pin "J3") (pinfunction "~{RAS}_J3") (pintype "input"))
      (node (ref "U4") (pin "J3") (pinfunction "~{RAS}_J3") (pintype "input"))
      (node (ref "U5") (pin "J3") (pinfunction "~{RAS}_J3") (pintype "input"))
    )
    (net (code "127") (name "/DRAM_RESET_B") (class "Default")
      (node (ref "R7") (pin "2") (pinfunction "2_2") (pintype "passive"))
      (node (ref "U1") (pin "Y6") (pinfunction "DRAM_RESET_Y6") (pintype "output"))
      (node (ref "U2") (pin "T2") (pinfunction "~{RESET}_T2") (pintype "input"))
      (node (ref "U3") (pin "T2") (pinfunction "~{RESET}_T2") (pintype "input"))
      (node (ref "U4") (pin "T2") (pinfunction "~{RESET}_T2") (pintype "input"))
      (node (ref "U5") (pin "T2") (pinfunction "~{RESET}_T2") (pintype "input"))
    )
    (net (code "128") (name "/DRAM_SDBA0") (class "Default")
      (node (ref "R2") (pin "1") (pinfunction "1_1") (pintype "passive"))
      (node (ref "U1") (pin "AC15") (pinfunction "DRAM_SDBA0_AC15") (pintype "output"))
      (node (ref "U2") (pin "M2") (pinfunction "BA0_M2") (pintype "input"))
      (node (ref "U3") (pin "M2") (pinfunction "BA0_M2") (pintype "input"))
      (node (ref "U4") (pin "M2") (pinfunction "BA0_M2") (pintype "input"))
      (node (ref "U5") (pin "M2") (pinfunction "BA0_M2") (pintype "input"))
    )
    (net (code "129") (name "/DRAM_SDBA1") (class "Default")
      (node (ref "R11") (pin "1") (pinfunction "1_1") (pintype "passive"))
      (node (ref "U1") (pin "Y15") (pinfunction "DRAM_SDBA1_Y15") (pintype "output"))
      (node (ref "U2") (pin "N8") (pinfunction "BA1_N8") (pintype "input"))
      (node (ref "U3") (pin "N8") (pinfunction "BA1_N8") (pintype "input"))
      (node (ref "U4") (pin "N8") (pinfunction "BA1_N8") (pintype "input"))
      (node (ref "U5") (pin "N8") (pinfunction "BA1_N8") (pintype "input"))
    )
    (net (code "130") (name "/DRAM_SDBA2") (class "Default")
      (node (ref "R22") (pin "1") (pinfunction "1_1") (pintype "passive"))
      (node (ref "U1") (pin "AB12") (pinfunction "DRAM_SDBA2_AB12") (pintype "output"))
      (node (ref "U2") (pin "M3") (pinfunction "BA2_M3") (pintype "input"))
      (node (ref "U3") (pin "M3") (pinfunction "BA2_M3") (pintype "input"))
      (node (ref "U4") (pin "M3") (pinfunction "BA2_M3") (pintype "input"))
      (node (ref "U5") (pin "M3") (pinfunction "BA2_M3") (pintype "input"))
    )
    (net (code "131") (name "/DRAM_SDCKE0") (class "Default")
      (node (ref "R45") (pin "1") (pinfunction "1_1") (pintype "passive"))
      (node (ref "R6") (pin "2") (pinfunction "2_2") (pintype "passive"))
      (node (ref "U1") (pin "Y11") (pinfunction "DRAM_SDCKE0_Y11") (pintype "output"))
      (node (ref "U2") (pin "K9") (pinfunction "CKE_K9") (pintype "input"))
      (node (ref "U3") (pin "K9") (pinfunction "CKE_K9") (pintype "input"))
      (node (ref "U4") (pin "K9") (pinfunction "CKE_K9") (pintype "input"))
      (node (ref "U5") (pin "K9") (pinfunction "CKE_K9") (pintype "input"))
    )
    (net (code "132") (name "/DRAM_SDODT0") (class "Default")
      (node (ref "R77") (pin "1") (pinfunction "1_1") (pintype "passive"))
      (node (ref "U1") (pin "AC16") (pinfunction "DRAM_SDODT0_AC16") (pintype "output"))
      (node (ref "U2") (pin "K1") (pinfunction "ODT_K1") (pintype "input"))
      (node (ref "U3") (pin "K1") (pinfunction "ODT_K1") (pintype "input"))
      (node (ref "U4") (pin "K1") (pinfunction "ODT_K1") (pintype "input"))
      (node (ref "U5") (pin "K1") (pinfunction "ODT_K1") (pintype "input"))
    )
    (net (code "133") (name "/DRAM_WE_B") (class "Default")
      (node (ref "R42") (pin "1") (pinfunction "1_1") (pintype "passive"))
      (node (ref "U1") (pin "AB16") (pinfunction "DRAM_SDWE_AB16") (pintype "output"))
      (node (ref "U2") (pin "L3") (pinfunction "~{WE}_L3") (pintype "input"))
      (node (ref "U3") (pin "L3") (pinfunction "~{WE}_L3") (pintype "input"))
      (node (ref "U4") (pin "L3") (pinfunction "~{WE}_L3") (pintype "input"))
      (node (ref "U5") (pin "L3") (pinfunction "~{WE}_L3") (pintype "input"))
    )
    (net (code "134") (name "/ZQPAD") (class "Default")
      (node (ref "R10") (pin "1") (pinfunction "1_1") (pintype "passive"))
      (node (ref "U1") (pin "AE17") (pinfunction "ZQPAD_AE17") (pintype "passive"))
    )
    (net (code "135") (name "GND") (class "Default")
      (node (ref "C1") (pin "2") (pinfunction "2_2") (pintype "passive"))
      (node (ref "C10") (pin "2") (pinfunction "2_2") (pintype "passive"))
      (node (ref "C11") (pin "2") (pinfunction "2_2") (pintype "passive"))
      (node (ref "C12") (pin "2") (pinfunction "2_2") (pintype "passive"))
      (node (ref "C19") (pin "2") (pinfunction "2_2") (pintype "passive"))
      (node (ref "C2") (pin "2") (pinfunction "2_2") (pintype "passive"))
      (node (ref "C203") (pin "2") (pinfunction "2_2") (pintype "passive"))
      (node (ref "C204") (pin "2") (pinfunction "2_2") (pintype "passive"))
      (node (ref "C205") (pin "2") (pinfunction "2_2") (pintype "passive"))
      (node (ref "C21") (pin "2") (pinfunction "2_2") (pintype "passive"))
      (node (ref "C22") (pin "2") (pinfunction "2_2") (pintype "passive"))
      (node (ref "C229") (pin "2") (pinfunction "2_2") (pintype "passive"))
      (node (ref "C23") (pin "2") (pinfunction "2_2") (pintype "passive"))
      (node (ref "C24") (pin "2") (pinfunction "2_2") (pintype "passive"))
      (node (ref "C25") (pin "2") (pinfunction "2_2") (pintype "passive"))
      (node (ref "C26") (pin "2") (pinfunction "2_2") (pintype "passive"))
      (node (ref "C27") (pin "2") (pinfunction "2_2") (pintype "passive"))
      (node (ref "C277") (pin "2") (pinfunction "2_2") (pintype "passive"))
      (node (ref "C28") (pin "2") (pinfunction "2_2") (pintype "passive"))
      (node (ref "C29") (pin "2") (pinfunction "2_2") (pintype "passive"))
      (node (ref "C297") (pin "2") (pinfunction "2_2") (pintype "passive"))
      (node (ref "C3") (pin "2") (pinfunction "2_2") (pintype "passive"))
      (node (ref "C30") (pin "2") (pinfunction "2_2") (pintype "passive"))
      (node (ref "C305") (pin "2") (pinfunction "2_2") (pintype "passive"))
      (node (ref "C306") (pin "2") (pinfunction "2_2") (pintype "passive"))
      (node (ref "C308") (pin "2") (pinfunction "2_2") (pintype "passive"))
      (node (ref "C31") (pin "2") (pinfunction "2_2") (pintype "passive"))
      (node (ref "C317") (pin "2") (pinfunction "2_2") (pintype "passive"))
      (node (ref "C318") (pin "2") (pinfunction "2_2") (pintype "passive"))
      (node (ref "C319") (pin "2") (pinfunction "2_2") (pintype "passive"))
      (node (ref "C32") (pin "2") (pinfunction "2_2") (pintype "passive"))
      (node (ref "C320") (pin "2") (pinfunction "2_2") (pintype "passive"))
      (node (ref "C321") (pin "2") (pinfunction "2_2") (pintype "passive"))
      (node (ref "C33") (pin "2") (pinfunction "2_2") (pintype "passive"))
      (node (ref "C34") (pin "2") (pinfunction "2_2") (pintype "passive"))
      (node (ref "C35") (pin "2") (pinfunction "2_2") (pintype "passive"))
      (node (ref "C36") (pin "2") (pinfunction "2_2") (pintype "passive"))
      (node (ref "C37") (pin "2") (pinfunction "2_2") (pintype "passive"))
      (node (ref "C38") (pin "2") (pinfunction "2_2") (pintype "passive"))
      (node (ref "C39") (pin "2") (pinfunction "2_2") (pintype "passive"))
      (node (ref "C393") (pin "2") (pinfunction "2_2") (pintype "passive"))
      (node (ref "C4") (pin "2") (pinfunction "2_2") (pintype "passive"))
      (node (ref "C40") (pin "2") (pinfunction "2_2") (pintype "passive"))
      (node (ref "C41") (pin "2") (pinfunction "2_2") (pintype "passive"))
      (node (ref "C42") (pin "2") (pinfunction "2_2") (pintype "passive"))
      (node (ref "C43") (pin "2") (pinfunction "2_2") (pintype "passive"))
      (node (ref "C44") (pin "2") (pinfunction "2_2") (pintype "passive"))
      (node (ref "C45") (pin "2") (pinfunction "2_2") (pintype "passive"))
      (node (ref "C46") (pin "2") (pinfunction "2_2") (pintype "passive"))
      (node (ref "C47") (pin "2") (pinfunction "2_2") (pintype "passive"))
      (node (ref "C48") (pin "2") (pinfunction "2_2") (pintype "passive"))
      (node (ref "C49") (pin "2") (pinfunction "2_2") (pintype "passive"))
      (node (ref "C5") (pin "2") (pinfunction "2_2") (pintype "passive"))
      (node (ref "C50") (pin "2") (pinfunction "2_2") (pintype "passive"))
      (node (ref "C51") (pin "2") (pinfunction "2_2") (pintype "passive"))
      (node (ref "C52") (pin "2") (pinfunction "2_2") (pintype "passive"))
      (node (ref "C53") (pin "2") (pinfunction "2_2") (pintype "passive"))
      (node (ref "C54") (pin "2") (pinfunction "2_2") (pintype "passive"))
      (node (ref "C55") (pin "2") (pinfunction "2_2") (pintype "passive"))
      (node (ref "C56") (pin "2") (pinfunction "2_2") (pintype "passive"))
      (node (ref "C57") (pin "2") (pinfunction "2_2") (pintype "passive"))
      (node (ref "C58") (pin "2") (pinfunction "2_2") (pintype "passive"))
      (node (ref "C59") (pin "2") (pinfunction "2_2") (pintype "passive"))
      (node (ref "C6") (pin "2") (pinfunction "2_2") (pintype "passive"))
      (node (ref "C60") (pin "2") (pinfunction "2_2") (pintype "passive"))
      (node (ref "C7") (pin "2") (pinfunction "2_2") (pintype "passive"))
      (node (ref "C8") (pin "2") (pinfunction "2_2") (pintype "passive"))
      (node (ref "C9") (pin "2") (pinfunction "2_2") (pintype "passive"))
      (node (ref "R10") (pin "2") (pinfunction "2_2") (pintype "passive"))
      (node (ref "R274") (pin "1") (pinfunction "1_1") (pintype "passive"))
      (node (ref "R306") (pin "1") (pinfunction "1_1") (pintype "passive"))
      (node (ref "R307") (pin "1") (pinfunction "1_1") (pintype "passive"))
      (node (ref "R308") (pin "1") (pinfunction "1_1") (pintype "passive"))
      (node (ref "R309") (pin "1") (pinfunction "1_1") (pintype "passive"))
      (node (ref "R4") (pin "1") (pinfunction "1_1") (pintype "passive"))
      (node (ref "R5") (pin "1") (pinfunction "1_1") (pintype "passive"))
      (node (ref "R6") (pin "1") (pinfunction "1_1") (pintype "passive"))
      (node (ref "R7") (pin "1") (pinfunction "1_1") (pintype "passive"))
      (node (ref "R8") (pin "1") (pinfunction "1_1") (pintype "passive"))
      (node (ref "R9") (pin "1") (pinfunction "1_1") (pintype "passive"))
      (node (ref "U2") (pin "A9") (pinfunction "VSS1_A9") (pintype "power_in"))
      (node (ref "U2") (pin "B1") (pinfunction "VSSQ1_B1") (pintype "power_in"))
      (node (ref "U2") (pin "B3") (pinfunction "VSS2_B3") (pintype "power_in"))
      (node (ref "U2") (pin "B9") (pinfunction "VSSQ2_B9") (pintype "power_in"))
      (node (ref "U2") (pin "D1") (pinfunction "VSSQ3_D1") (pintype "power_in"))
      (node (ref "U2") (pin "D8") (pinfunction "VSSQ4_D8") (pintype "power_in"))
      (node (ref "U2") (pin "E1") (pinfunction "VSS3_E1") (pintype "power_in"))
      (node (ref "U2") (pin "E2") (pinfunction "VSSQ5_E2") (pintype "power_in"))
      (node (ref "U2") (pin "E8") (pinfunction "VSSQ6_E8") (pintype "power_in"))
      (node (ref "U2") (pin "F9") (pinfunction "VSSQ7_F9") (pintype "power_in"))
      (node (ref "U2") (pin "G1") (pinfunction "VSSQ8_G1") (pintype "power_in"))
      (node (ref "U2") (pin "G8") (pinfunction "VSS4_G8") (pintype "power_in"))
      (node (ref "U2") (pin "G9") (pinfunction "VSSQ9_G9") (pintype "power_in"))
      (node (ref "U2") (pin "J2") (pinfunction "VSS5_J2") (pintype "power_in"))
      (node (ref "U2") (pin "J8") (pinfunction "VSS6_J8") (pintype "power_in"))
      (node (ref "U2") (pin "M1") (pinfunction "VSS7_M1") (pintype "power_in"))
      (node (ref "U2") (pin "M9") (pinfunction "VSS8_M9") (pintype "power_in"))
      (node (ref "U2") (pin "P1") (pinfunction "VSS9_P1") (pintype "power_in"))
      (node (ref "U2") (pin "P9") (pinfunction "VSS10_P9") (pintype "power_in"))
      (node (ref "U2") (pin "T1") (pinfunction "VSS11_T1") (pintype "power_in"))
      (node (ref "U2") (pin "T9") (pinfunction "VSS12_T9") (pintype "power_in"))
      (node (ref "U3") (pin "A9") (pinfunction "VSS1_A9") (pintype "power_in"))
      (node (ref "U3") (pin "B1") (pinfunction "VSSQ1_B1") (pintype "power_in"))
      (node (ref "U3") (pin "B3") (pinfunction "VSS2_B3") (pintype "power_in"))
      (node (ref "U3") (pin "B9") (pinfunction "VSSQ2_B9") (pintype "power_in"))
      (node (ref "U3") (pin "D1") (pinfunction "VSSQ3_D1") (pintype "power_in"))
      (node (ref "U3") (pin "D8") (pinfunction "VSSQ4_D8") (pintype "power_in"))
      (node (ref "U3") (pin "E1") (pinfunction "VSS3_E1") (pintype "power_in"))
      (node (ref "U3") (pin "E2") (pinfunction "VSSQ5_E2") (pintype "power_in"))
      (node (ref "U3") (pin "E8") (pinfunction "VSSQ6_E8") (pintype "power_in"))
      (node (ref "U3") (pin "F9") (pinfunction "VSSQ7_F9") (pintype "power_in"))
      (node (ref "U3") (pin "G1") (pinfunction "VSSQ8_G1") (pintype "power_in"))
      (node (ref "U3") (pin "G8") (pinfunction "VSS4_G8") (pintype "power_in"))
      (node (ref "U3") (pin "G9") (pinfunction "VSSQ9_G9") (pintype "power_in"))
      (node (ref "U3") (pin "J2") (pinfunction "VSS5_J2") (pintype "power_in"))
      (node (ref "U3") (pin "J8") (pinfunction "VSS6_J8") (pintype "power_in"))
      (node (ref "U3") (pin "M1") (pinfunction "VSS7_M1") (pintype "power_in"))
      (node (ref "U3") (pin "M9") (pinfunction "VSS8_M9") (pintype "power_in"))
      (node (ref "U3") (pin "P1") (pinfunction "VSS9_P1") (pintype "power_in"))
      (node (ref "U3") (pin "P9") (pinfunction "VSS10_P9") (pintype "power_in"))
      (node (ref "U3") (pin "T1") (pinfunction "VSS11_T1") (pintype "power_in"))
      (node (ref "U3") (pin "T9") (pinfunction "VSS12_T9") (pintype "power_in"))
      (node (ref "U4") (pin "A9") (pinfunction "VSS1_A9") (pintype "power_in"))
      (node (ref "U4") (pin "B1") (pinfunction "VSSQ1_B1") (pintype "power_in"))
      (node (ref "U4") (pin "B3") (pinfunction "VSS2_B3") (pintype "power_in"))
      (node (ref "U4") (pin "B9") (pinfunction "VSSQ2_B9") (pintype "power_in"))
      (node (ref "U4") (pin "D1") (pinfunction "VSSQ3_D1") (pintype "power_in"))
      (node (ref "U4") (pin "D8") (pinfunction "VSSQ4_D8") (pintype "power_in"))
      (node (ref "U4") (pin "E1") (pinfunction "VSS3_E1") (pintype "power_in"))
      (node (ref "U4") (pin "E2") (pinfunction "VSSQ5_E2") (pintype "power_in"))
      (node (ref "U4") (pin "E8") (pinfunction "VSSQ6_E8") (pintype "power_in"))
      (node (ref "U4") (pin "F9") (pinfunction "VSSQ7_F9") (pintype "power_in"))
      (node (ref "U4") (pin "G1") (pinfunction "VSSQ8_G1") (pintype "power_in"))
      (node (ref "U4") (pin "G8") (pinfunction "VSS4_G8") (pintype "power_in"))
      (node (ref "U4") (pin "G9") (pinfunction "VSSQ9_G9") (pintype "power_in"))
      (node (ref "U4") (pin "J2") (pinfunction "VSS5_J2") (pintype "power_in"))
      (node (ref "U4") (pin "J8") (pinfunction "VSS6_J8") (pintype "power_in"))
      (node (ref "U4") (pin "M1") (pinfunction "VSS7_M1") (pintype "power_in"))
      (node (ref "U4") (pin "M9") (pinfunction "VSS8_M9") (pintype "power_in"))
      (node (ref "U4") (pin "P1") (pinfunction "VSS9_P1") (pintype "power_in"))
      (node (ref "U4") (pin "P9") (pinfunction "VSS10_P9") (pintype "power_in"))
      (node (ref "U4") (pin "T1") (pinfunction "VSS11_T1") (pintype "power_in"))
      (node (ref "U4") (pin "T9") (pinfunction "VSS12_T9") (pintype "power_in"))
      (node (ref "U5") (pin "A9") (pinfunction "VSS1_A9") (pintype "power_in"))
      (node (ref "U5") (pin "B1") (pinfunction "VSSQ1_B1") (pintype "power_in"))
      (node (ref "U5") (pin "B3") (pinfunction "VSS2_B3") (pintype "power_in"))
      (node (ref "U5") (pin "B9") (pinfunction "VSSQ2_B9") (pintype "power_in"))
      (node (ref "U5") (pin "D1") (pinfunction "VSSQ3_D1") (pintype "power_in"))
      (node (ref "U5") (pin "D8") (pinfunction "VSSQ4_D8") (pintype "power_in"))
      (node (ref "U5") (pin "E1") (pinfunction "VSS3_E1") (pintype "power_in"))
      (node (ref "U5") (pin "E2") (pinfunction "VSSQ5_E2") (pintype "power_in"))
      (node (ref "U5") (pin "E8") (pinfunction "VSSQ6_E8") (pintype "power_in"))
      (node (ref "U5") (pin "F9") (pinfunction "VSSQ7_F9") (pintype "power_in"))
      (node (ref "U5") (pin "G1") (pinfunction "VSSQ8_G1") (pintype "power_in"))
      (node (ref "U5") (pin "G8") (pinfunction "VSS4_G8") (pintype "power_in"))
      (node (ref "U5") (pin "G9") (pinfunction "VSSQ9_G9") (pintype "power_in"))
      (node (ref "U5") (pin "J2") (pinfunction "VSS5_J2") (pintype "power_in"))
      (node (ref "U5") (pin "J8") (pinfunction "VSS6_J8") (pintype "power_in"))
      (node (ref "U5") (pin "M1") (pinfunction "VSS7_M1") (pintype "power_in"))
      (node (ref "U5") (pin "M9") (pinfunction "VSS8_M9") (pintype "power_in"))
      (node (ref "U5") (pin "P1") (pinfunction "VSS9_P1") (pintype "power_in"))
      (node (ref "U5") (pin "P9") (pinfunction "VSS10_P9") (pintype "power_in"))
      (node (ref "U5") (pin "T1") (pinfunction "VSS11_T1") (pintype "power_in"))
      (node (ref "U5") (pin "T9") (pinfunction "VSS12_T9") (pintype "power_in"))
    )
    (net (code "136") (name "unconnected-(U1C-DRAM_CS1-PadAD17)") (class "Default")
      (node (ref "U1") (pin "AD17") (pinfunction "DRAM_CS1_AD17") (pintype "output+no_connect"))
    )
    (net (code "137") (name "unconnected-(U1C-DRAM_SDCKE1-PadAA11)") (class "Default")
      (node (ref "U1") (pin "AA11") (pinfunction "DRAM_SDCKE1_AA11") (pintype "output+no_connect"))
    )
    (net (code "138") (name "unconnected-(U1C-DRAM_SDODT1-PadAB17)") (class "Default")
      (node (ref "U1") (pin "AB17") (pinfunction "DRAM_SDODT1_AB17") (pintype "output+no_connect"))
    )
    (net (code "139") (name "unconnected-(U2-NC_J1-PadJ1)") (class "Default")
      (node (ref "U2") (pin "J1") (pinfunction "NC_J1_J1") (pintype "passive+no_connect"))
    )
    (net (code "140") (name "unconnected-(U2-NC_J9-PadJ9)") (class "Default")
      (node (ref "U2") (pin "J9") (pinfunction "NC_J9_J9") (pintype "passive+no_connect"))
    )
    (net (code "141") (name "unconnected-(U2-NC_L1-PadL1)") (class "Default")
      (node (ref "U2") (pin "L1") (pinfunction "NC_L1_L1") (pintype "passive+no_connect"))
    )
    (net (code "142") (name "unconnected-(U3-NC_J1-PadJ1)") (class "Default")
      (node (ref "U3") (pin "J1") (pinfunction "NC_J1_J1") (pintype "passive+no_connect"))
    )
    (net (code "143") (name "unconnected-(U3-NC_J9-PadJ9)") (class "Default")
      (node (ref "U3") (pin "J9") (pinfunction "NC_J9_J9") (pintype "passive+no_connect"))
    )
    (net (code "144") (name "unconnected-(U3-NC_L1-PadL1)") (class "Default")
      (node (ref "U3") (pin "L1") (pinfunction "NC_L1_L1") (pintype "passive+no_connect"))
    )
    (net (code "145") (name "unconnected-(U4-NC_J1-PadJ1)") (class "Default")
      (node (ref "U4") (pin "J1") (pinfunction "NC_J1_J1") (pintype "passive+no_connect"))
    )
    (net (code "146") (name "unconnected-(U4-NC_J9-PadJ9)") (class "Default")
      (node (ref "U4") (pin "J9") (pinfunction "NC_J9_J9") (pintype "passive+no_connect"))
    )
    (net (code "147") (name "unconnected-(U4-NC_L1-PadL1)") (class "Default")
      (node (ref "U4") (pin "L1") (pinfunction "NC_L1_L1") (pintype "passive+no_connect"))
    )
    (net (code "148") (name "unconnected-(U5-NC_J1-PadJ1)") (class "Default")
      (node (ref "U5") (pin "J1") (pinfunction "NC_J1_J1") (pintype "passive+no_connect"))
    )
    (net (code "149") (name "unconnected-(U5-NC_J9-PadJ9)") (class "Default")
      (node (ref "U5") (pin "J9") (pinfunction "NC_J9_J9") (pintype "passive+no_connect"))
    )
    (net (code "150") (name "unconnected-(U5-NC_L1-PadL1)") (class "Default")
      (node (ref "U5") (pin "L1") (pinfunction "NC_L1_L1") (pintype "passive+no_connect"))
    )
  )
)
